# ElectroLab.net
KiCad netlist of a schematic drawn in EAGLE
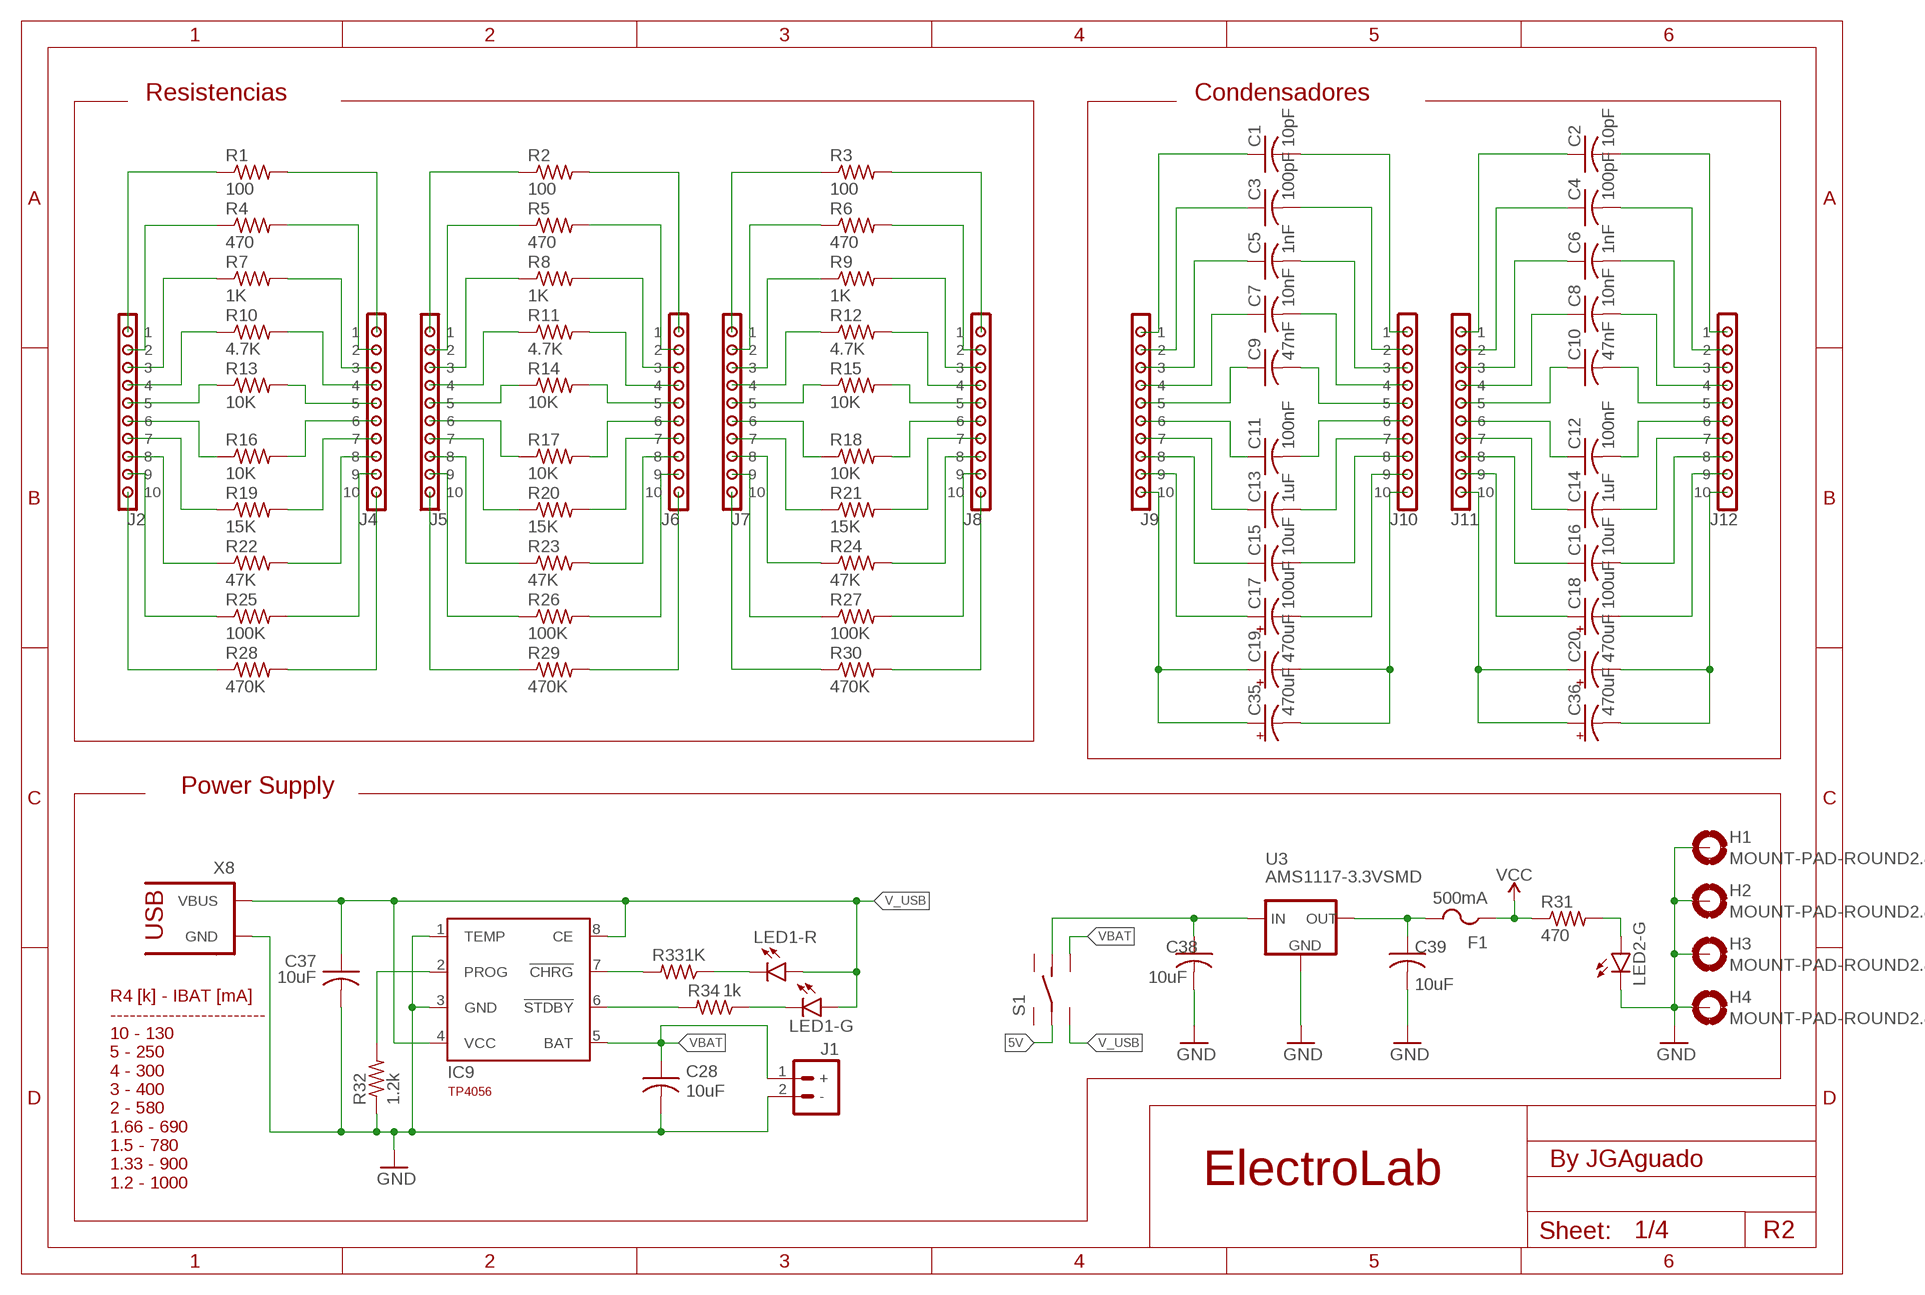
[diagram p0: schematic, sheet 1]
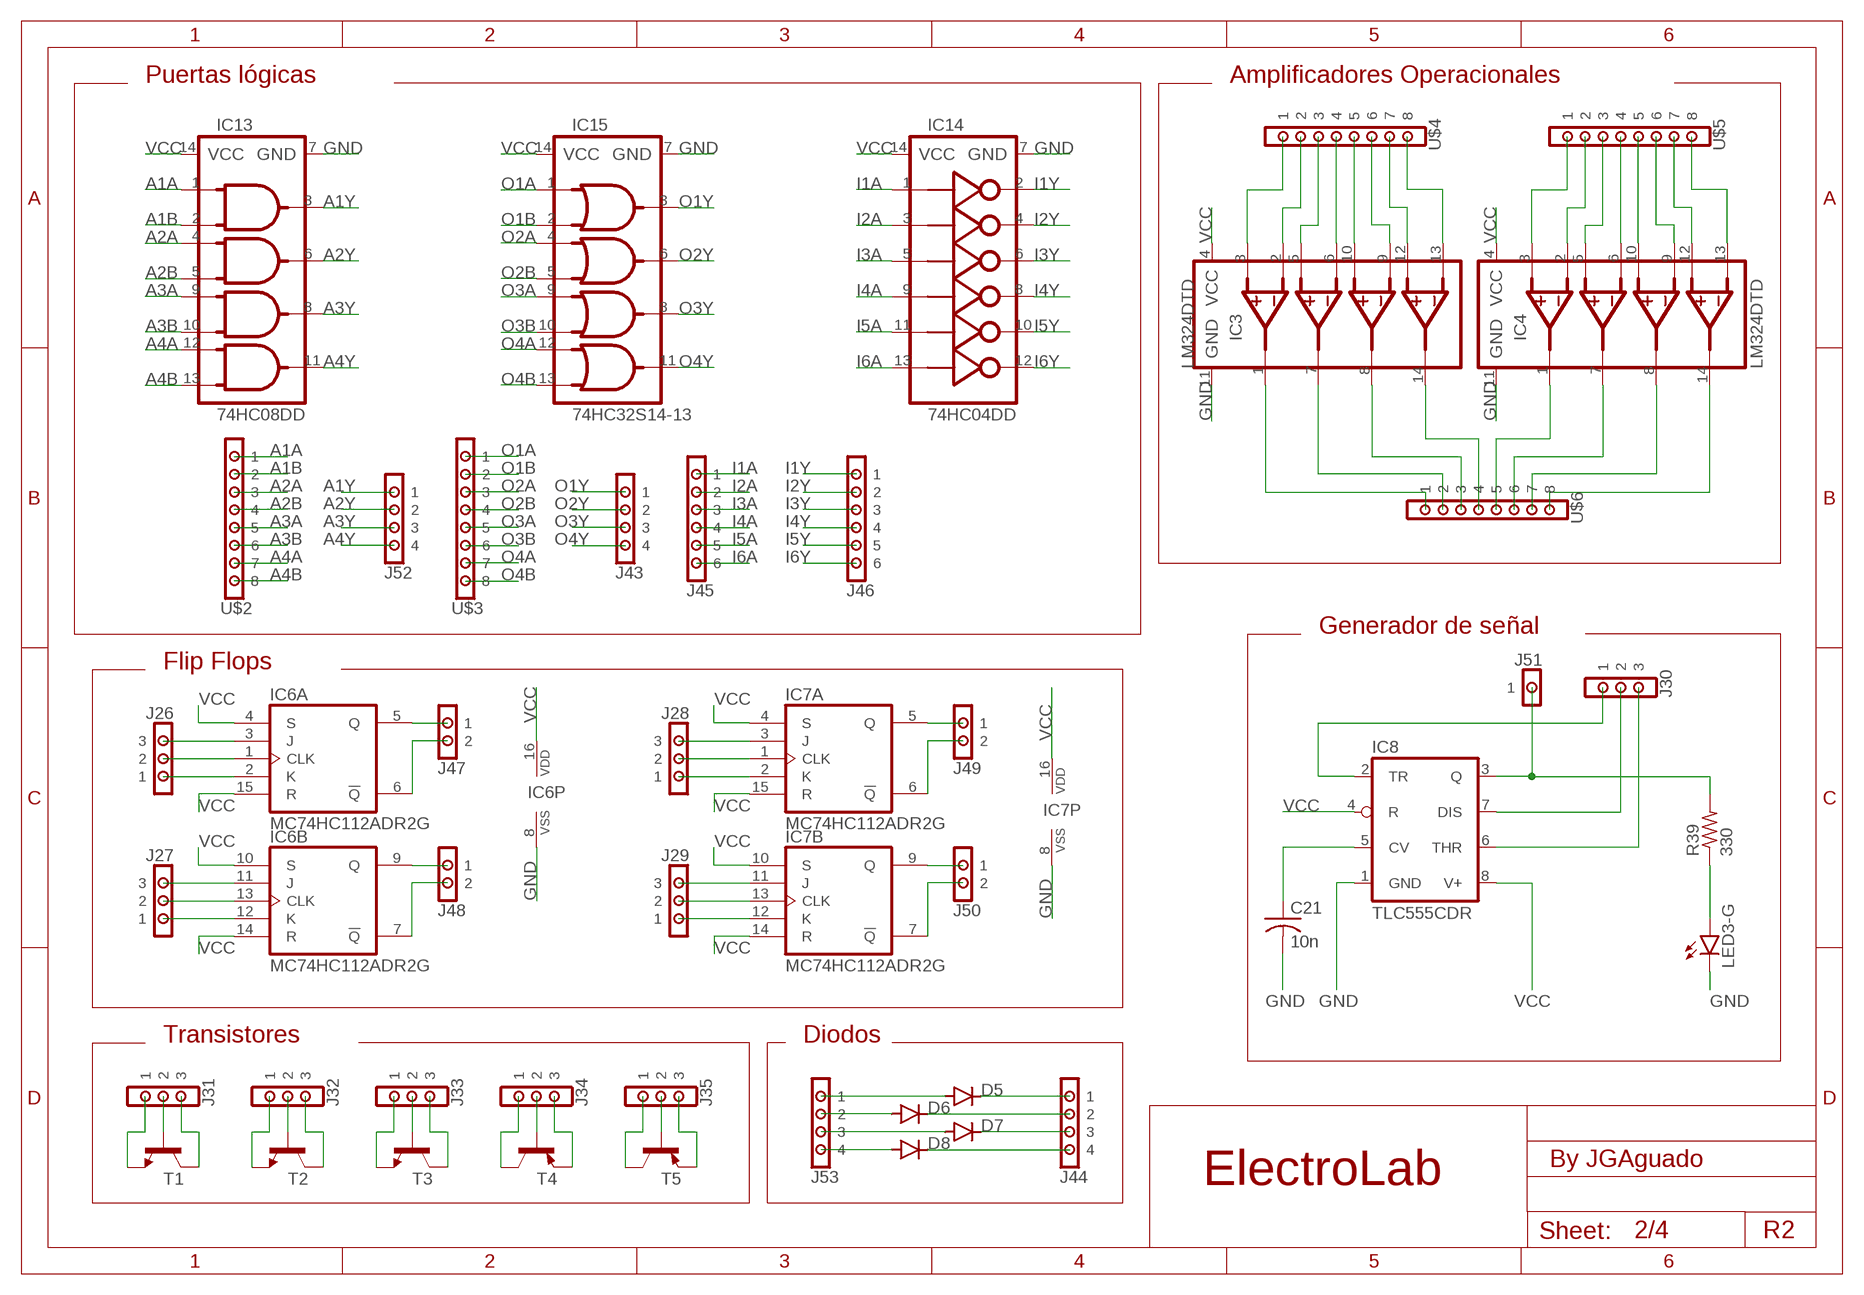
[diagram p1: schematic, sheet 2]
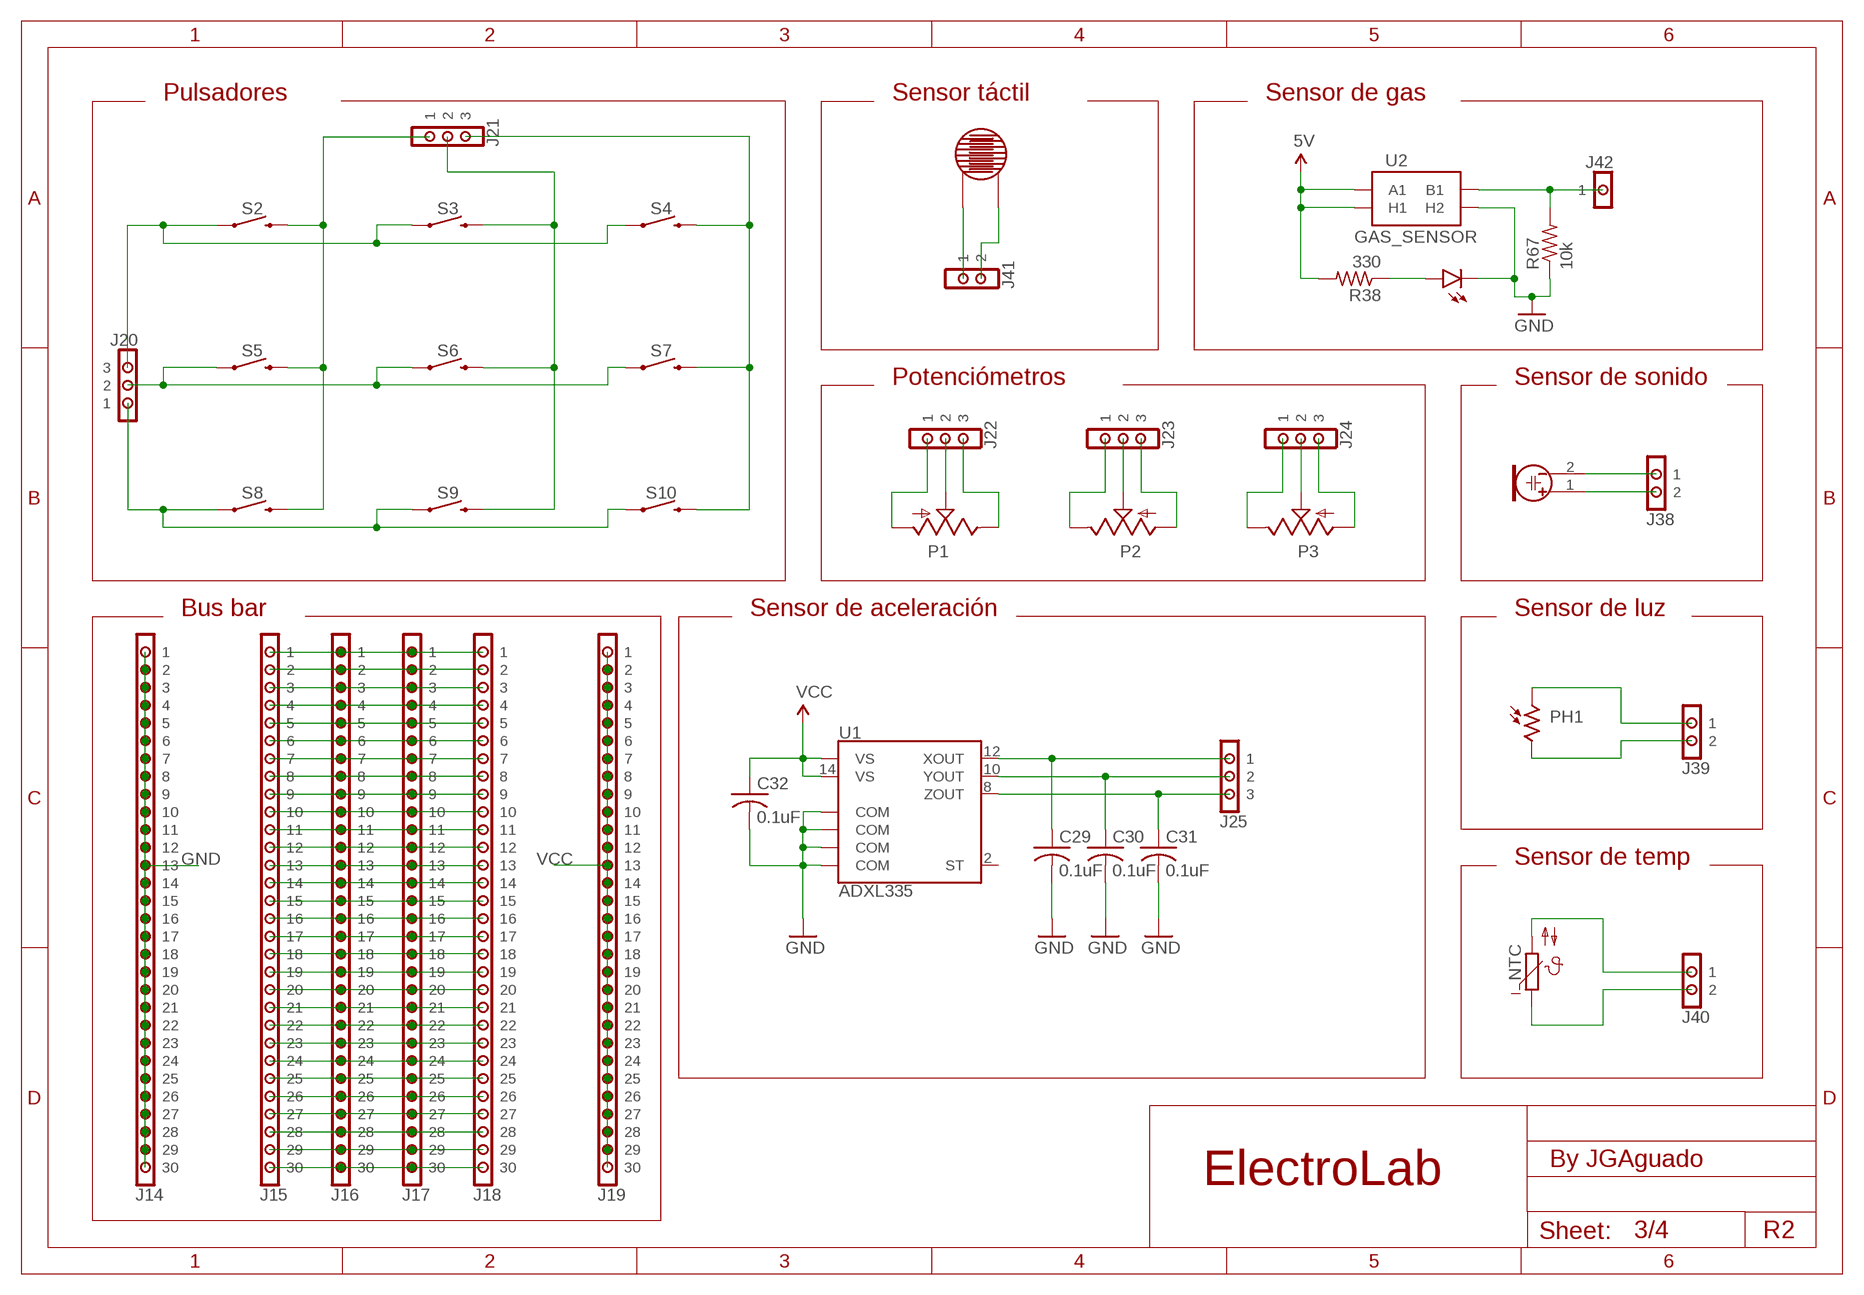
[diagram p2: schematic, sheet 3]
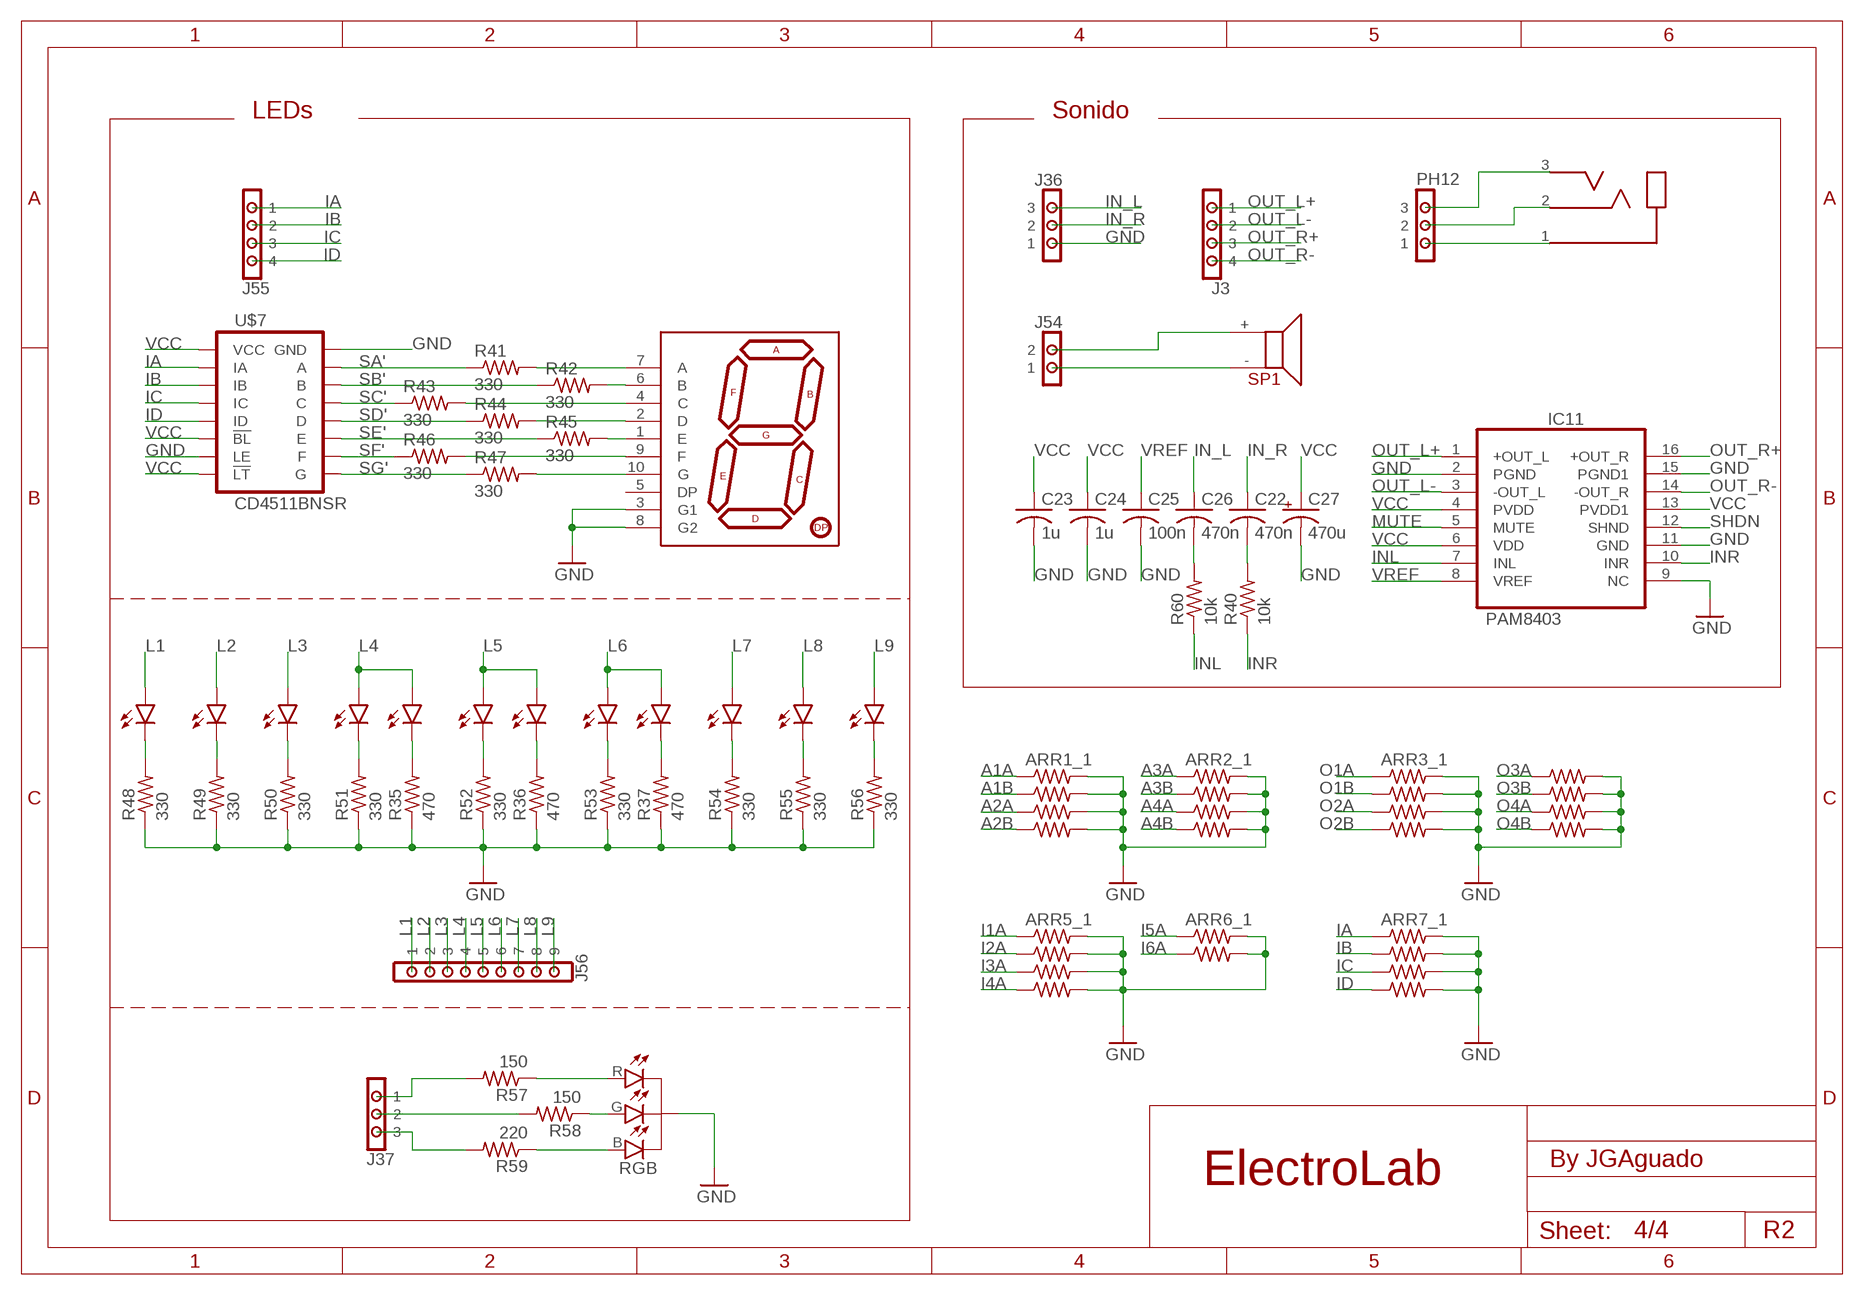
[diagram p3: schematic, sheet 4]

(export (version "E")
  (design (tool "Eeschema 10.0.6"))
  (components
    (comp (ref "C1")
      (value "10pF")
      (footprint "eagle-import:0603")
      (libsource (lib "eagle-import") (part "C0603"))
    )
    (comp (ref "C2")
      (value "10pF")
      (footprint "eagle-import:0603")
      (libsource (lib "eagle-import") (part "C0603"))
    )
    (comp (ref "C3")
      (value "100pF")
      (footprint "eagle-import:0603")
      (libsource (lib "eagle-import") (part "C0603"))
    )
    (comp (ref "C4")
      (value "100pF")
      (footprint "eagle-import:0603")
      (libsource (lib "eagle-import") (part "C0603"))
    )
    (comp (ref "C5")
      (value "1nF")
      (footprint "eagle-import:0603")
      (libsource (lib "eagle-import") (part "C0603"))
    )
    (comp (ref "C6")
      (value "1nF")
      (footprint "eagle-import:0603")
      (libsource (lib "eagle-import") (part "C0603"))
    )
    (comp (ref "C7")
      (value "10nF")
      (footprint "eagle-import:0603")
      (libsource (lib "eagle-import") (part "C0603"))
    )
    (comp (ref "C8")
      (value "10nF")
      (footprint "eagle-import:0603")
      (libsource (lib "eagle-import") (part "C0603"))
    )
    (comp (ref "C9")
      (value "47nF")
      (footprint "eagle-import:0603")
      (libsource (lib "eagle-import") (part "C0603"))
    )
    (comp (ref "C10")
      (value "47nF")
      (footprint "eagle-import:0603")
      (libsource (lib "eagle-import") (part "C0603"))
    )
    (comp (ref "C11")
      (value "100nF")
      (footprint "eagle-import:0603")
      (libsource (lib "eagle-import") (part "C0603"))
    )
    (comp (ref "C12")
      (value "100nF")
      (footprint "eagle-import:0603")
      (libsource (lib "eagle-import") (part "C0603"))
    )
    (comp (ref "C13")
      (value "1uF")
      (footprint "eagle-import:0603")
      (libsource (lib "eagle-import") (part "C0603"))
    )
    (comp (ref "C14")
      (value "1uF")
      (footprint "eagle-import:0603")
      (libsource (lib "eagle-import") (part "C0603"))
    )
    (comp (ref "C15")
      (value "10uF")
      (footprint "eagle-import:0603")
      (libsource (lib "eagle-import") (part "C0603"))
    )
    (comp (ref "C16")
      (value "10uF")
      (footprint "eagle-import:0603")
      (libsource (lib "eagle-import") (part "C0603"))
    )
    (comp (ref "C17")
      (value "100uF")
      (footprint "eagle-import:B_3528-21R")
      (libsource (lib "eagle-import") (part "C3528"))
    )
    (comp (ref "C18")
      (value "100uF")
      (footprint "eagle-import:B_3528-21R")
      (libsource (lib "eagle-import") (part "C3528"))
    )
    (comp (ref "C19")
      (value "470uF")
      (footprint "eagle-import:D_7343-31R")
      (libsource (lib "eagle-import") (part "C7343"))
    )
    (comp (ref "C20")
      (value "470uF")
      (footprint "eagle-import:D_7343-31R")
      (libsource (lib "eagle-import") (part "C7343"))
    )
    (comp (ref "C28")
      (value "10uF")
      (footprint "eagle-import:C0603")
      (libsource (lib "eagle-import") (part "C-USC0603"))
    )
    (comp (ref "C35")
      (value "470uF")
      (footprint "eagle-import:D_7343-31R")
      (libsource (lib "eagle-import") (part "C7343"))
    )
    (comp (ref "C36")
      (value "470uF")
      (footprint "eagle-import:D_7343-31R")
      (libsource (lib "eagle-import") (part "C7343"))
    )
    (comp (ref "C37")
      (value "10uF")
      (footprint "eagle-import:C0603")
      (libsource (lib "eagle-import") (part "C-USC0603"))
    )
    (comp (ref "C38")
      (value "10uF")
      (footprint "eagle-import:C0603")
      (libsource (lib "eagle-import") (part "C-USC0603"))
    )
    (comp (ref "C39")
      (value "10uF")
      (footprint "eagle-import:C0603")
      (libsource (lib "eagle-import") (part "C-USC0603"))
    )
    (comp (ref "F1")
      (value "500mA")
      (footprint "eagle-import:R1206")
      (libsource (lib "eagle-import") (part "PTCFUSE-1206"))
    )
    (comp (ref "H1")
      (value "MOUNT-PAD-ROUND2.8")
      (footprint "eagle-import:2,8-PAD")
      (libsource (lib "eagle-import") (part "MOUNT-PAD-ROUND2.8"))
    )
    (comp (ref "H2")
      (value "MOUNT-PAD-ROUND2.8")
      (footprint "eagle-import:2,8-PAD")
      (libsource (lib "eagle-import") (part "MOUNT-PAD-ROUND2.8"))
    )
    (comp (ref "H3")
      (value "MOUNT-PAD-ROUND2.8")
      (footprint "eagle-import:2,8-PAD")
      (libsource (lib "eagle-import") (part "MOUNT-PAD-ROUND2.8"))
    )
    (comp (ref "H4")
      (value "MOUNT-PAD-ROUND2.8")
      (footprint "eagle-import:2,8-PAD")
      (libsource (lib "eagle-import") (part "MOUNT-PAD-ROUND2.8"))
    )
    (comp (ref "IC9")
      (value "TP4056")
      (footprint "eagle-import:SOT23-8")
      (libsource (lib "eagle-import") (part "TP4056"))
    )
    (comp (ref "J1")
      (value "BAT_CONN-JST-2MM-SMT")
      (footprint "eagle-import:JST-2-SMD")
      (fields (field (name "LCSC") "C3029440"))
      (libsource (lib "eagle-import") (part "BAT_CONN-JST-2MM-SMT"))
    )
    (comp (ref "J2")
      (value "CONN_10\"")
      (footprint "eagle-import:1X10")
      (libsource (lib "eagle-import") (part "CONN_10{dblquote}"))
    )
    (comp (ref "J4")
      (value "CONN_10\"")
      (footprint "eagle-import:1X10")
      (libsource (lib "eagle-import") (part "CONN_10{dblquote}"))
    )
    (comp (ref "J5")
      (value "CONN_10\"")
      (footprint "eagle-import:1X10")
      (libsource (lib "eagle-import") (part "CONN_10{dblquote}"))
    )
    (comp (ref "J6")
      (value "CONN_10\"")
      (footprint "eagle-import:1X10")
      (libsource (lib "eagle-import") (part "CONN_10{dblquote}"))
    )
    (comp (ref "J7")
      (value "CONN_10\"")
      (footprint "eagle-import:1X10")
      (libsource (lib "eagle-import") (part "CONN_10{dblquote}"))
    )
    (comp (ref "J8")
      (value "CONN_10\"")
      (footprint "eagle-import:1X10")
      (libsource (lib "eagle-import") (part "CONN_10{dblquote}"))
    )
    (comp (ref "J9")
      (value "CONN_10\"")
      (footprint "eagle-import:1X10")
      (libsource (lib "eagle-import") (part "CONN_10{dblquote}"))
    )
    (comp (ref "J10")
      (value "CONN_10\"")
      (footprint "eagle-import:1X10")
      (libsource (lib "eagle-import") (part "CONN_10{dblquote}"))
    )
    (comp (ref "J11")
      (value "CONN_10\"")
      (footprint "eagle-import:1X10")
      (libsource (lib "eagle-import") (part "CONN_10{dblquote}"))
    )
    (comp (ref "J12")
      (value "CONN_10\"")
      (footprint "eagle-import:1X10")
      (libsource (lib "eagle-import") (part "CONN_10{dblquote}"))
    )
    (comp (ref "LED1")
      (value "E6CC1205RYGC2UDA")
      (footprint "eagle-import:BICOLOR_LED")
      (libsource (lib "eagle-import") (part "RED&GREEN_LED"))
    )
    (comp (ref "LED2")
      (value "E6CC1205RYGC2UDA")
      (footprint "eagle-import:BICOLOR_LED")
      (libsource (lib "eagle-import") (part "RED&GREEN_LED"))
    )
    (comp (ref "R1")
      (value "100")
      (footprint "eagle-import:0603")
      (libsource (lib "eagle-import") (part "R0603"))
    )
    (comp (ref "R2")
      (value "100")
      (footprint "eagle-import:0603")
      (libsource (lib "eagle-import") (part "R0603"))
    )
    (comp (ref "R3")
      (value "100")
      (footprint "eagle-import:0603")
      (libsource (lib "eagle-import") (part "R0603"))
    )
    (comp (ref "R4")
      (value "470")
      (footprint "eagle-import:0603")
      (libsource (lib "eagle-import") (part "R0603"))
    )
    (comp (ref "R5")
      (value "470")
      (footprint "eagle-import:0603")
      (libsource (lib "eagle-import") (part "R0603"))
    )
    (comp (ref "R6")
      (value "470")
      (footprint "eagle-import:0603")
      (libsource (lib "eagle-import") (part "R0603"))
    )
    (comp (ref "R7")
      (value "1K")
      (footprint "eagle-import:0603")
      (libsource (lib "eagle-import") (part "R0603"))
    )
    (comp (ref "R8")
      (value "1K")
      (footprint "eagle-import:0603")
      (libsource (lib "eagle-import") (part "R0603"))
    )
    (comp (ref "R9")
      (value "1K")
      (footprint "eagle-import:0603")
      (libsource (lib "eagle-import") (part "R0603"))
    )
    (comp (ref "R10")
      (value "4.7K")
      (footprint "eagle-import:0603")
      (libsource (lib "eagle-import") (part "R0603"))
    )
    (comp (ref "R11")
      (value "4.7K")
      (footprint "eagle-import:0603")
      (libsource (lib "eagle-import") (part "R0603"))
    )
    (comp (ref "R12")
      (value "4.7K")
      (footprint "eagle-import:0603")
      (libsource (lib "eagle-import") (part "R0603"))
    )
    (comp (ref "R13")
      (value "10K")
      (footprint "eagle-import:0603")
      (libsource (lib "eagle-import") (part "R0603"))
    )
    (comp (ref "R14")
      (value "10K")
      (footprint "eagle-import:0603")
      (libsource (lib "eagle-import") (part "R0603"))
    )
    (comp (ref "R15")
      (value "10K")
      (footprint "eagle-import:0603")
      (libsource (lib "eagle-import") (part "R0603"))
    )
    (comp (ref "R16")
      (value "10K")
      (footprint "eagle-import:0603")
      (libsource (lib "eagle-import") (part "R0603"))
    )
    (comp (ref "R17")
      (value "10K")
      (footprint "eagle-import:0603")
      (libsource (lib "eagle-import") (part "R0603"))
    )
    (comp (ref "R18")
      (value "10K")
      (footprint "eagle-import:0603")
      (libsource (lib "eagle-import") (part "R0603"))
    )
    (comp (ref "R19")
      (value "15K")
      (footprint "eagle-import:0603")
      (libsource (lib "eagle-import") (part "R0603"))
    )
    (comp (ref "R20")
      (value "15K")
      (footprint "eagle-import:0603")
      (libsource (lib "eagle-import") (part "R0603"))
    )
    (comp (ref "R21")
      (value "15K")
      (footprint "eagle-import:0603")
      (libsource (lib "eagle-import") (part "R0603"))
    )
    (comp (ref "R22")
      (value "47K")
      (footprint "eagle-import:0603")
      (libsource (lib "eagle-import") (part "R0603"))
    )
    (comp (ref "R23")
      (value "47K")
      (footprint "eagle-import:0603")
      (libsource (lib "eagle-import") (part "R0603"))
    )
    (comp (ref "R24")
      (value "47K")
      (footprint "eagle-import:0603")
      (libsource (lib "eagle-import") (part "R0603"))
    )
    (comp (ref "R25")
      (value "100K")
      (footprint "eagle-import:0603")
      (libsource (lib "eagle-import") (part "R0603"))
    )
    (comp (ref "R26")
      (value "100K")
      (footprint "eagle-import:0603")
      (libsource (lib "eagle-import") (part "R0603"))
    )
    (comp (ref "R27")
      (value "100K")
      (footprint "eagle-import:0603")
      (libsource (lib "eagle-import") (part "R0603"))
    )
    (comp (ref "R28")
      (value "470K")
      (footprint "eagle-import:0603")
      (libsource (lib "eagle-import") (part "R0603"))
    )
    (comp (ref "R29")
      (value "470K")
      (footprint "eagle-import:0603")
      (libsource (lib "eagle-import") (part "R0603"))
    )
    (comp (ref "R30")
      (value "470K")
      (footprint "eagle-import:0603")
      (libsource (lib "eagle-import") (part "R0603"))
    )
    (comp (ref "R31")
      (value "470")
      (footprint "eagle-import:0603")
      (libsource (lib "eagle-import") (part "R0603"))
    )
    (comp (ref "R32")
      (value "1.2k")
      (footprint "eagle-import:R0603")
      (libsource (lib "eagle-import") (part "R-US_R0603"))
    )
    (comp (ref "R33")
      (value "1K")
      (footprint "eagle-import:0603")
      (libsource (lib "eagle-import") (part "R0603"))
    )
    (comp (ref "R34")
      (value "1k")
      (footprint "eagle-import:0603")
      (libsource (lib "eagle-import") (part "R0603"))
    )
    (comp (ref "S1")
      (value "DPDT_JS202011CQN")
      (footprint "eagle-import:DPDT_JS202011CQN")
      (libsource (lib "eagle-import") (part "DPDT_JS202011CQN"))
    )
    (comp (ref "U3")
      (value "AMS1117-3.3VSMD")
      (footprint "eagle-import:SOT223")
      (libsource (lib "eagle-import") (part "AMS1117-SMD3.3V"))
    )
    (comp (ref "X8")
      (value "USB-C-POWER")
      (footprint "eagle-import:USB-C-POWER")
      (libsource (lib "eagle-import") (part "USB-C-POWER"))
    )
    (comp (ref "C21")
      (value "10n")
      (footprint "eagle-import:0603")
      (libsource (lib "eagle-import") (part "C0603"))
    )
    (comp (ref "D5")
      (value "LL4148")
      (footprint "eagle-import:LL-34")
      (fields (field (name "MOUSER_PART_NUMBER") "512-LL4148"))
      (libsource (lib "eagle-import") (part "LL4148"))
    )
    (comp (ref "D6")
      (value "LL4148")
      (footprint "eagle-import:LL-34")
      (fields (field (name "MOUSER_PART_NUMBER") "512-LL4148"))
      (libsource (lib "eagle-import") (part "LL4148"))
    )
    (comp (ref "D7")
      (value "LL4148")
      (footprint "eagle-import:LL-34")
      (fields (field (name "MOUSER_PART_NUMBER") "512-LL4148"))
      (libsource (lib "eagle-import") (part "LL4148"))
    )
    (comp (ref "D8")
      (value "LL4148")
      (footprint "eagle-import:LL-34")
      (fields (field (name "MOUSER_PART_NUMBER") "512-LL4148"))
      (libsource (lib "eagle-import") (part "LL4148"))
    )
    (comp (ref "IC3")
      (value "LM324DTD")
      (footprint "eagle-import:SO14")
      (libsource (lib "eagle-import") (part "LM324DTD"))
    )
    (comp (ref "IC4")
      (value "LM324DTD")
      (footprint "eagle-import:SO14")
      (libsource (lib "eagle-import") (part "LM324DTD"))
    )
    (comp (ref "IC6")
      (value "MC74HC112ADR2G")
      (footprint "eagle-import:SO16")
      (libsource (lib "eagle-import") (part "JK_FLIP_FLOPMC74HC112ADR2G"))
    )
    (comp (ref "IC7")
      (value "MC74HC112ADR2G")
      (footprint "eagle-import:SO16")
      (libsource (lib "eagle-import") (part "JK_FLIP_FLOPMC74HC112ADR2G"))
    )
    (comp (ref "IC8")
      (value "TLC555CDR")
      (footprint "eagle-import:SO08")
      (libsource (lib "eagle-import") (part "555DNE"))
    )
    (comp (ref "IC13")
      (value "74HC08DD")
      (footprint "eagle-import:SO14")
      (libsource (lib "eagle-import") (part "74HC08DD"))
    )
    (comp (ref "IC14")
      (value "74HC04DD")
      (footprint "eagle-import:SO14")
      (libsource (lib "eagle-import") (part "74HC04DD"))
    )
    (comp (ref "IC15")
      (value "74HC32S14-13")
      (footprint "eagle-import:SO14")
      (fields (field (name "LCSC") "C176921"))
      (libsource (lib "eagle-import") (part "74AHC32D74HC32S14-13"))
    )
    (comp (ref "J26")
      (value "CONN_03")
      (footprint "eagle-import:1X03")
      (libsource (lib "eagle-import") (part "CONN_03"))
    )
    (comp (ref "J27")
      (value "CONN_03")
      (footprint "eagle-import:1X03")
      (libsource (lib "eagle-import") (part "CONN_03"))
    )
    (comp (ref "J28")
      (value "CONN_03")
      (footprint "eagle-import:1X03")
      (libsource (lib "eagle-import") (part "CONN_03"))
    )
    (comp (ref "J29")
      (value "CONN_03")
      (footprint "eagle-import:1X03")
      (libsource (lib "eagle-import") (part "CONN_03"))
    )
    (comp (ref "J30")
      (value "CONN_03")
      (footprint "eagle-import:1X03")
      (libsource (lib "eagle-import") (part "CONN_03"))
    )
    (comp (ref "J31")
      (value "CONN_03")
      (footprint "eagle-import:1X03")
      (libsource (lib "eagle-import") (part "CONN_03"))
    )
    (comp (ref "J32")
      (value "CONN_03")
      (footprint "eagle-import:1X03")
      (libsource (lib "eagle-import") (part "CONN_03"))
    )
    (comp (ref "J33")
      (value "CONN_03")
      (footprint "eagle-import:1X03")
      (libsource (lib "eagle-import") (part "CONN_03"))
    )
    (comp (ref "J34")
      (value "CONN_03")
      (footprint "eagle-import:1X03")
      (libsource (lib "eagle-import") (part "CONN_03"))
    )
    (comp (ref "J35")
      (value "CONN_03")
      (footprint "eagle-import:1X03")
      (libsource (lib "eagle-import") (part "CONN_03"))
    )
    (comp (ref "J43")
      (value "CONN_04")
      (footprint "eagle-import:1X04")
      (libsource (lib "eagle-import") (part "CONN_04"))
    )
    (comp (ref "J44")
      (value "CONN_04")
      (footprint "eagle-import:1X04")
      (libsource (lib "eagle-import") (part "CONN_04"))
    )
    (comp (ref "J45")
      (value "CONN_06")
      (footprint "eagle-import:1X06")
      (libsource (lib "eagle-import") (part "CONN_06"))
    )
    (comp (ref "J46")
      (value "CONN_06")
      (footprint "eagle-import:1X06")
      (libsource (lib "eagle-import") (part "CONN_06"))
    )
    (comp (ref "J47")
      (value "CONN_02")
      (footprint "eagle-import:1X02")
      (libsource (lib "eagle-import") (part "CONN_02"))
    )
    (comp (ref "J48")
      (value "CONN_02")
      (footprint "eagle-import:1X02")
      (libsource (lib "eagle-import") (part "CONN_02"))
    )
    (comp (ref "J49")
      (value "CONN_02")
      (footprint "eagle-import:1X02")
      (libsource (lib "eagle-import") (part "CONN_02"))
    )
    (comp (ref "J50")
      (value "CONN_02")
      (footprint "eagle-import:1X02")
      (libsource (lib "eagle-import") (part "CONN_02"))
    )
    (comp (ref "J51")
      (value "CONN_01")
      (footprint "eagle-import:1X01")
      (libsource (lib "eagle-import") (part "CONN_01"))
    )
    (comp (ref "J52")
      (value "CONN_04")
      (footprint "eagle-import:1X04")
      (libsource (lib "eagle-import") (part "CONN_04"))
    )
    (comp (ref "J53")
      (value "CONN_04")
      (footprint "eagle-import:1X04")
      (libsource (lib "eagle-import") (part "CONN_04"))
    )
    (comp (ref "LED3")
      (value "E6CC1205RYGC2UDA")
      (footprint "eagle-import:BICOLOR_LED")
      (libsource (lib "eagle-import") (part "RED&GREEN_LED"))
    )
    (comp (ref "R39")
      (value "330")
      (footprint "eagle-import:0603")
      (libsource (lib "eagle-import") (part "R0603"))
    )
    (comp (ref "T1")
      (value "MMBT2222A")
      (footprint "eagle-import:SOT23")
      (fields (field (name "LCSC_PART") "C8512"))
      (libsource (lib "eagle-import") (part "T_NPN_SOT23-BECMMBT2222A-1P_CHANGJ"))
    )
    (comp (ref "T2")
      (value "T_NPNMMBT2222A-1P_CHANGJ_SOT23-BEC")
      (footprint "eagle-import:SOT23")
      (fields (field (name "LCSC_PART") "C8512"))
      (libsource (lib "eagle-import") (part "T_NPN_SOT23-BECMMBT2222A-1P_CHANGJ"))
    )
    (comp (ref "T3")
      (value "T_NPNMMBT2222A-1P_CHANGJ_SOT23-BEC")
      (footprint "eagle-import:SOT23")
      (fields (field (name "LCSC_PART") "C8512"))
      (libsource (lib "eagle-import") (part "T_NPN_SOT23-BECMMBT2222A-1P_CHANGJ"))
    )
    (comp (ref "T4")
      (value "T_PNPMMBT5401_CHANGJ_SOT23-BEC")
      (footprint "eagle-import:SOT23")
      (fields (field (name "LCSC_PART") "C8326"))
      (libsource (lib "eagle-import") (part "T_PNP_SOT23-BECMMBT5401_CHANGJ"))
    )
    (comp (ref "T5")
      (value "T_PNPMMBT5401_CHANGJ_SOT23-BEC")
      (footprint "eagle-import:SOT23")
      (fields (field (name "LCSC_PART") "C8326"))
      (libsource (lib "eagle-import") (part "T_PNP_SOT23-BECMMBT5401_CHANGJ"))
    )
    (comp (ref "U$2")
      (value "CONN_08")
      (footprint "eagle-import:1X08")
      (libsource (lib "eagle-import") (part "CONN_08"))
    )
    (comp (ref "U$3")
      (value "CONN_08")
      (footprint "eagle-import:1X08")
      (libsource (lib "eagle-import") (part "CONN_08"))
    )
    (comp (ref "U$4")
      (value "CONN_08")
      (footprint "eagle-import:1X08")
      (libsource (lib "eagle-import") (part "CONN_08"))
    )
    (comp (ref "U$5")
      (value "CONN_08")
      (footprint "eagle-import:1X08")
      (libsource (lib "eagle-import") (part "CONN_08"))
    )
    (comp (ref "U$6")
      (value "CONN_08")
      (footprint "eagle-import:1X08")
      (libsource (lib "eagle-import") (part "CONN_08"))
    )
    (comp (ref "C29")
      (value "0.1uF")
      (footprint "eagle-import:0603")
      (libsource (lib "eagle-import") (part "C0603"))
    )
    (comp (ref "C30")
      (value "0.1uF")
      (footprint "eagle-import:0603")
      (libsource (lib "eagle-import") (part "C0603"))
    )
    (comp (ref "C31")
      (value "0.1uF")
      (footprint "eagle-import:0603")
      (libsource (lib "eagle-import") (part "C0603"))
    )
    (comp (ref "C32")
      (value "0.1uF")
      (footprint "eagle-import:0603")
      (libsource (lib "eagle-import") (part "C0603"))
    )
    (comp (ref "J14")
      (value "CONN_30")
      (footprint "eagle-import:1X30")
      (libsource (lib "eagle-import") (part "CONN_30"))
    )
    (comp (ref "J15")
      (value "CONN_30")
      (footprint "eagle-import:1X30")
      (libsource (lib "eagle-import") (part "CONN_30"))
    )
    (comp (ref "J16")
      (value "CONN_30")
      (footprint "eagle-import:1X30")
      (libsource (lib "eagle-import") (part "CONN_30"))
    )
    (comp (ref "J17")
      (value "CONN_30")
      (footprint "eagle-import:1X30")
      (libsource (lib "eagle-import") (part "CONN_30"))
    )
    (comp (ref "J18")
      (value "CONN_30")
      (footprint "eagle-import:1X30")
      (libsource (lib "eagle-import") (part "CONN_30"))
    )
    (comp (ref "J19")
      (value "CONN_30")
      (footprint "eagle-import:1X30")
      (libsource (lib "eagle-import") (part "CONN_30"))
    )
    (comp (ref "J20")
      (value "CONN_03")
      (footprint "eagle-import:1X03")
      (libsource (lib "eagle-import") (part "CONN_03"))
    )
    (comp (ref "J21")
      (value "CONN_03")
      (footprint "eagle-import:1X03")
      (libsource (lib "eagle-import") (part "CONN_03"))
    )
    (comp (ref "J22")
      (value "CONN_03")
      (footprint "eagle-import:1X03")
      (libsource (lib "eagle-import") (part "CONN_03"))
    )
    (comp (ref "J23")
      (value "CONN_03")
      (footprint "eagle-import:1X03")
      (libsource (lib "eagle-import") (part "CONN_03"))
    )
    (comp (ref "J24")
      (value "CONN_03")
      (footprint "eagle-import:1X03")
      (libsource (lib "eagle-import") (part "CONN_03"))
    )
    (comp (ref "J25")
      (value "CONN_03")
      (footprint "eagle-import:1X03")
      (libsource (lib "eagle-import") (part "CONN_03"))
    )
    (comp (ref "J38")
      (value "CONN_02")
      (footprint "eagle-import:1X02")
      (libsource (lib "eagle-import") (part "CONN_02"))
    )
    (comp (ref "J39")
      (value "CONN_02")
      (footprint "eagle-import:1X02")
      (libsource (lib "eagle-import") (part "CONN_02"))
    )
    (comp (ref "J40")
      (value "CONN_02")
      (footprint "eagle-import:1X02")
      (libsource (lib "eagle-import") (part "CONN_02"))
    )
    (comp (ref "J41")
      (value "CONN_02")
      (footprint "eagle-import:1X02")
      (libsource (lib "eagle-import") (part "CONN_02"))
    )
    (comp (ref "J42")
      (value "CONN_01")
      (footprint "eagle-import:1X01")
      (libsource (lib "eagle-import") (part "CONN_01"))
    )
    (comp (ref "LED13")
      (value "E6CC1205RYGC2UDA")
      (footprint "eagle-import:BICOLOR_LED")
      (libsource (lib "eagle-import") (part "RED&GREEN_LED"))
    )
    (comp (ref "MIC")
      (value "MICROPHONE")
      (footprint "eagle-import:MICROPHONE")
      (libsource (lib "eagle-import") (part "MICROPHONE"))
    )
    (comp (ref "NTC")
      (value "THERMISTOR")
      (footprint "eagle-import:NTC")
      (libsource (lib "eagle-import") (part "THERMISTOR"))
    )
    (comp (ref "P1")
      (value "SLIDE_POT_20MM")
      (footprint "eagle-import:RS201111J011")
      (libsource (lib "eagle-import") (part "SLIDE_POT_20MM"))
    )
    (comp (ref "P2")
      (value "ALPS_RK09K_VERTICAL")
      (footprint "eagle-import:ALPS_RK09K_VERTICAL")
      (libsource (lib "eagle-import") (part "ALPS_RK09K_VERTICAL"))
    )
    (comp (ref "P3")
      (value "ALPS_RK09K_VERTICAL")
      (footprint "eagle-import:ALPS_RK09K_VERTICAL")
      (libsource (lib "eagle-import") (part "ALPS_RK09K_VERTICAL"))
    )
    (comp (ref "PH1")
      (value "PHOTORESISTOR")
      (footprint "eagle-import:GL5516")
      (libsource (lib "eagle-import") (part "PHOTORESISTOR"))
    )
    (comp (ref "R38")
      (value "330")
      (footprint "eagle-import:0603")
      (libsource (lib "eagle-import") (part "R0603"))
    )
    (comp (ref "R67")
      (value "10k")
      (footprint "eagle-import:0603")
      (libsource (lib "eagle-import") (part "R0603"))
    )
    (comp (ref "S2")
      (value "MOMENTARY-SWITCH-SPST-PTH-6.0MM")
      (footprint "eagle-import:TACTILE_SWITCH_PTH_6.0MM")
      (libsource (lib "eagle-import") (part "MOMENTARY-SWITCH-SPST-PTH-6.0MM"))
    )
    (comp (ref "S3")
      (value "MOMENTARY-SWITCH-SPST-PTH-6.0MM")
      (footprint "eagle-import:TACTILE_SWITCH_PTH_6.0MM")
      (libsource (lib "eagle-import") (part "MOMENTARY-SWITCH-SPST-PTH-6.0MM"))
    )
    (comp (ref "S4")
      (value "MOMENTARY-SWITCH-SPST-PTH-6.0MM")
      (footprint "eagle-import:TACTILE_SWITCH_PTH_6.0MM")
      (libsource (lib "eagle-import") (part "MOMENTARY-SWITCH-SPST-PTH-6.0MM"))
    )
    (comp (ref "S5")
      (value "MOMENTARY-SWITCH-SPST-PTH-6.0MM")
      (footprint "eagle-import:TACTILE_SWITCH_PTH_6.0MM")
      (libsource (lib "eagle-import") (part "MOMENTARY-SWITCH-SPST-PTH-6.0MM"))
    )
    (comp (ref "S6")
      (value "MOMENTARY-SWITCH-SPST-PTH-6.0MM")
      (footprint "eagle-import:TACTILE_SWITCH_PTH_6.0MM")
      (libsource (lib "eagle-import") (part "MOMENTARY-SWITCH-SPST-PTH-6.0MM"))
    )
    (comp (ref "S7")
      (value "MOMENTARY-SWITCH-SPST-PTH-6.0MM")
      (footprint "eagle-import:TACTILE_SWITCH_PTH_6.0MM")
      (libsource (lib "eagle-import") (part "MOMENTARY-SWITCH-SPST-PTH-6.0MM"))
    )
    (comp (ref "S8")
      (value "MOMENTARY-SWITCH-SPST-PTH-6.0MM")
      (footprint "eagle-import:TACTILE_SWITCH_PTH_6.0MM")
      (libsource (lib "eagle-import") (part "MOMENTARY-SWITCH-SPST-PTH-6.0MM"))
    )
    (comp (ref "S9")
      (value "MOMENTARY-SWITCH-SPST-PTH-6.0MM")
      (footprint "eagle-import:TACTILE_SWITCH_PTH_6.0MM")
      (libsource (lib "eagle-import") (part "MOMENTARY-SWITCH-SPST-PTH-6.0MM"))
    )
    (comp (ref "S10")
      (value "MOMENTARY-SWITCH-SPST-PTH-6.0MM")
      (footprint "eagle-import:TACTILE_SWITCH_PTH_6.0MM")
      (libsource (lib "eagle-import") (part "MOMENTARY-SWITCH-SPST-PTH-6.0MM"))
    )
    (comp (ref "U$16")
      (value "RESISTIVE_SENSOR_PAD")
      (footprint "eagle-import:RESISTIVE_SENSOR_PAD")
      (libsource (lib "eagle-import") (part "RESISTIVE_SENSOR_PAD"))
    )
    (comp (ref "U1")
      (value "ADXL335")
      (footprint "eagle-import:LFCSP-16-4X4")
      (libsource (lib "eagle-import") (part "ADXL335"))
    )
    (comp (ref "U2")
      (value "GAS_SENSOR")
      (footprint "eagle-import:GAS_SENSOR")
      (libsource (lib "eagle-import") (part "GAS_SENSORMQ-3"))
    )
    (comp (ref "ARR1")
      (value "4_RES_ARRAY_R06031KOHM")
      (footprint "eagle-import:0603-ARC")
      (libsource (lib "eagle-import") (part "4_RES_ARRAY_R06031KOHM"))
    )
    (comp (ref "ARR2")
      (value "4_RES_ARRAY_R06031KOHM")
      (footprint "eagle-import:0603-ARC")
      (libsource (lib "eagle-import") (part "4_RES_ARRAY_R06031KOHM"))
    )
    (comp (ref "ARR3")
      (value "4_RES_ARRAY_R06031KOHM")
      (footprint "eagle-import:0603-ARC")
      (libsource (lib "eagle-import") (part "4_RES_ARRAY_R06031KOHM"))
    )
    (comp (ref "ARR4")
      (value "4_RES_ARRAY_R06031KOHM")
      (footprint "eagle-import:0603-ARC")
      (libsource (lib "eagle-import") (part "4_RES_ARRAY_R06031KOHM"))
    )
    (comp (ref "ARR5")
      (value "4_RES_ARRAY_R06031KOHM")
      (footprint "eagle-import:0603-ARC")
      (libsource (lib "eagle-import") (part "4_RES_ARRAY_R06031KOHM"))
    )
    (comp (ref "ARR6")
      (value "4_RES_ARRAY_R06031KOHM")
      (footprint "eagle-import:0603-ARC")
      (libsource (lib "eagle-import") (part "4_RES_ARRAY_R06031KOHM"))
    )
    (comp (ref "ARR7")
      (value "4_RES_ARRAY_R06031KOHM")
      (footprint "eagle-import:0603-ARC")
      (libsource (lib "eagle-import") (part "4_RES_ARRAY_R06031KOHM"))
    )
    (comp (ref "C22")
      (value "470n")
      (footprint "eagle-import:0603")
      (libsource (lib "eagle-import") (part "C0603"))
    )
    (comp (ref "C23")
      (value "1u")
      (footprint "eagle-import:0603")
      (libsource (lib "eagle-import") (part "C0603"))
    )
    (comp (ref "C24")
      (value "1u")
      (footprint "eagle-import:0603")
      (libsource (lib "eagle-import") (part "C0603"))
    )
    (comp (ref "C25")
      (value "100n")
      (footprint "eagle-import:0603")
      (libsource (lib "eagle-import") (part "C0603"))
    )
    (comp (ref "C26")
      (value "470n")
      (footprint "eagle-import:0603")
      (libsource (lib "eagle-import") (part "C0603"))
    )
    (comp (ref "C27")
      (value "470u")
      (footprint "eagle-import:D_7343-31R")
      (fields (field (name "LCSC") "C7229"))
      (libsource (lib "eagle-import") (part "C7343"))
    )
    (comp (ref "IC11")
      (value "PAM8403")
      (footprint "eagle-import:SOP-16")
      (libsource (lib "eagle-import") (part "PAM8403"))
    )
    (comp (ref "J3")
      (value "CONN_04")
      (footprint "eagle-import:1X04")
      (libsource (lib "eagle-import") (part "CONN_04"))
    )
    (comp (ref "J36")
      (value "CONN_03")
      (footprint "eagle-import:1X03")
      (libsource (lib "eagle-import") (part "CONN_03"))
    )
    (comp (ref "J37")
      (value "CONN_03")
      (footprint "eagle-import:1X03")
      (libsource (lib "eagle-import") (part "CONN_03"))
    )
    (comp (ref "J54")
      (value "CONN_02")
      (footprint "eagle-import:1X02")
      (libsource (lib "eagle-import") (part "CONN_02"))
    )
    (comp (ref "J55")
      (value "CONN_04")
      (footprint "eagle-import:1X04")
      (libsource (lib "eagle-import") (part "CONN_04"))
    )
    (comp (ref "J56")
      (value "CONN_09")
      (footprint "eagle-import:1X09")
      (libsource (lib "eagle-import") (part "CONN_09"))
    )
    (comp (ref "JACK")
      (value "AUDIO_JACK_MONO_3.5_3P")
      (footprint "eagle-import:HC-PJ-320A-3P-D")
      (libsource (lib "eagle-import") (part "AUDIO_JACK_MONO_3.5_3P"))
    )
    (comp (ref "LED4")
      (value "E6CC1205RYGC2UDA")
      (footprint "eagle-import:BICOLOR_LED")
      (libsource (lib "eagle-import") (part "RED&GREEN_LED"))
    )
    (comp (ref "LED5")
      (value "E6CC1205RYGC2UDA")
      (footprint "eagle-import:BICOLOR_LED")
      (libsource (lib "eagle-import") (part "RED&GREEN_LED"))
    )
    (comp (ref "LED6")
      (value "E6CC1205RYGC2UDA")
      (footprint "eagle-import:BICOLOR_LED")
      (libsource (lib "eagle-import") (part "RED&GREEN_LED"))
    )
    (comp (ref "LED7")
      (value "E6CC1205RYGC2UDA")
      (footprint "eagle-import:BICOLOR_LED")
      (libsource (lib "eagle-import") (part "RED&GREEN_LED"))
    )
    (comp (ref "LED8")
      (value "E6CC1205RYGC2UDA")
      (footprint "eagle-import:BICOLOR_LED")
      (libsource (lib "eagle-import") (part "RED&GREEN_LED"))
    )
    (comp (ref "LED9")
      (value "E6CC1205RYGC2UDA")
      (footprint "eagle-import:BICOLOR_LED")
      (libsource (lib "eagle-import") (part "RED&GREEN_LED"))
    )
    (comp (ref "LED10")
      (value "E6CC1205RYGC2UDA")
      (footprint "eagle-import:BICOLOR_LED")
      (libsource (lib "eagle-import") (part "RED&GREEN_LED"))
    )
    (comp (ref "LED11")
      (value "E6CC1205RYGC2UDA")
      (footprint "eagle-import:BICOLOR_LED")
      (libsource (lib "eagle-import") (part "RED&GREEN_LED"))
    )
    (comp (ref "LED12")
      (value "E6CC1205RYGC2UDA")
      (footprint "eagle-import:BICOLOR_LED")
      (libsource (lib "eagle-import") (part "RED&GREEN_LED"))
    )
    (comp (ref "PH12")
      (value "CONN_03")
      (footprint "eagle-import:1X03")
      (libsource (lib "eagle-import") (part "CONN_03"))
    )
    (comp (ref "R35")
      (value "470")
      (footprint "eagle-import:0603")
      (libsource (lib "eagle-import") (part "R0603"))
    )
    (comp (ref "R36")
      (value "470")
      (footprint "eagle-import:0603")
      (libsource (lib "eagle-import") (part "R0603"))
    )
    (comp (ref "R37")
      (value "470")
      (footprint "eagle-import:0603")
      (libsource (lib "eagle-import") (part "R0603"))
    )
    (comp (ref "R40")
      (value "10k")
      (footprint "eagle-import:0603")
      (libsource (lib "eagle-import") (part "R0603"))
    )
    (comp (ref "R41")
      (value "330")
      (footprint "eagle-import:0603")
      (libsource (lib "eagle-import") (part "R0603"))
    )
    (comp (ref "R42")
      (value "330")
      (footprint "eagle-import:0603")
      (libsource (lib "eagle-import") (part "R0603"))
    )
    (comp (ref "R43")
      (value "330")
      (footprint "eagle-import:0603")
      (libsource (lib "eagle-import") (part "R0603"))
    )
    (comp (ref "R44")
      (value "330")
      (footprint "eagle-import:0603")
      (libsource (lib "eagle-import") (part "R0603"))
    )
    (comp (ref "R45")
      (value "330")
      (footprint "eagle-import:0603")
      (libsource (lib "eagle-import") (part "R0603"))
    )
    (comp (ref "R46")
      (value "330")
      (footprint "eagle-import:0603")
      (libsource (lib "eagle-import") (part "R0603"))
    )
    (comp (ref "R47")
      (value "330")
      (footprint "eagle-import:0603")
      (libsource (lib "eagle-import") (part "R0603"))
    )
    (comp (ref "R48")
      (value "330")
      (footprint "eagle-import:0603")
      (libsource (lib "eagle-import") (part "R0603"))
    )
    (comp (ref "R49")
      (value "330")
      (footprint "eagle-import:0603")
      (libsource (lib "eagle-import") (part "R0603"))
    )
    (comp (ref "R50")
      (value "330")
      (footprint "eagle-import:0603")
      (libsource (lib "eagle-import") (part "R0603"))
    )
    (comp (ref "R51")
      (value "330")
      (footprint "eagle-import:0603")
      (libsource (lib "eagle-import") (part "R0603"))
    )
    (comp (ref "R52")
      (value "330")
      (footprint "eagle-import:0603")
      (libsource (lib "eagle-import") (part "R0603"))
    )
    (comp (ref "R53")
      (value "330")
      (footprint "eagle-import:0603")
      (libsource (lib "eagle-import") (part "R0603"))
    )
    (comp (ref "R54")
      (value "330")
      (footprint "eagle-import:0603")
      (libsource (lib "eagle-import") (part "R0603"))
    )
    (comp (ref "R55")
      (value "330")
      (footprint "eagle-import:0603")
      (libsource (lib "eagle-import") (part "R0603"))
    )
    (comp (ref "R56")
      (value "330")
      (footprint "eagle-import:0603")
      (libsource (lib "eagle-import") (part "R0603"))
    )
    (comp (ref "R57")
      (value "150")
      (footprint "eagle-import:0603")
      (libsource (lib "eagle-import") (part "R0603"))
    )
    (comp (ref "R58")
      (value "150")
      (footprint "eagle-import:0603")
      (libsource (lib "eagle-import") (part "R0603"))
    )
    (comp (ref "R59")
      (value "220")
      (footprint "eagle-import:0603")
      (libsource (lib "eagle-import") (part "R0603"))
    )
    (comp (ref "R60")
      (value "10k")
      (footprint "eagle-import:0603")
      (libsource (lib "eagle-import") (part "R0603"))
    )
    (comp (ref "RGB")
      (value "CLEAR")
      (footprint "eagle-import:LED-RGB-THRU")
      (libsource (lib "eagle-import") (part "LED-RGB-CCCLEAR"))
    )
    (comp (ref "SP1")
      (value "SPEAKERFS1508MB0810-H8.0")
      (footprint "eagle-import:FS1508MB0810-H8.0")
      (fields (field (name "MANUFACTURER") "FUET"))
      (libsource (lib "eagle-import") (part "SPEAKERFS1508MB0810-H8.0"))
    )
    (comp (ref "U$1")
      (value "FJ5101AG")
      (footprint "eagle-import:7-SEGMENT")
      (libsource (lib "eagle-import") (part "7-SEGMENT-1DIGIT-GREEN"))
    )
    (comp (ref "U$7")
      (value "CD4511BNSR")
      (footprint "eagle-import:SO16")
      (libsource (lib "eagle-import") (part "CD4511BNSR"))
    )
  )
  (nets
    (net (code "1") (name "5V") (class "Default")
      (node (ref "R38") (pin "2") (pinfunction "2_2") (pintype "passive"))
      (node (ref "S1") (pin "2") (pinfunction "LC_2") (pintype "passive"))
      (node (ref "U2") (pin "A1") (pinfunction "A1_A1") (pintype "bidirectional"))
      (node (ref "U2") (pin "HA") (pinfunction "H1_HA") (pintype "bidirectional"))
    )
    (net (code "2") (name "A1A") (class "Default")
      (node (ref "ARR1") (pin "1") (pinfunction "1_1") (pintype "passive"))
      (node (ref "IC13") (pin "1") (pinfunction "1A_1") (pintype "input"))
      (node (ref "U$2") (pin "1") (pinfunction "1_1") (pintype "passive"))
    )
    (net (code "3") (name "A1B") (class "Default")
      (node (ref "ARR1") (pin "2") (pinfunction "1_2") (pintype "passive"))
      (node (ref "IC13") (pin "2") (pinfunction "1B_2") (pintype "input"))
      (node (ref "U$2") (pin "2") (pinfunction "2_2") (pintype "passive"))
    )
    (net (code "4") (name "A1Y") (class "Default")
      (node (ref "IC13") (pin "3") (pinfunction "1Y_3") (pintype "output"))
      (node (ref "J52") (pin "1") (pinfunction "1_1") (pintype "passive"))
    )
    (net (code "5") (name "A2A") (class "Default")
      (node (ref "ARR1") (pin "3") (pinfunction "1_3") (pintype "passive"))
      (node (ref "IC13") (pin "4") (pinfunction "2A_4") (pintype "input"))
      (node (ref "U$2") (pin "3") (pinfunction "3_3") (pintype "passive"))
    )
    (net (code "6") (name "A2B") (class "Default")
      (node (ref "ARR1") (pin "4") (pinfunction "1_4") (pintype "passive"))
      (node (ref "IC13") (pin "5") (pinfunction "2B_5") (pintype "input"))
      (node (ref "U$2") (pin "4") (pinfunction "4_4") (pintype "passive"))
    )
    (net (code "7") (name "A2Y") (class "Default")
      (node (ref "IC13") (pin "6") (pinfunction "2Y_6") (pintype "output"))
      (node (ref "J52") (pin "2") (pinfunction "2_2") (pintype "passive"))
    )
    (net (code "8") (name "A3A") (class "Default")
      (node (ref "ARR2") (pin "1") (pinfunction "1_1") (pintype "passive"))
      (node (ref "IC13") (pin "9") (pinfunction "3A_9") (pintype "input"))
      (node (ref "U$2") (pin "5") (pinfunction "5_5") (pintype "passive"))
    )
    (net (code "9") (name "A3B") (class "Default")
      (node (ref "ARR2") (pin "2") (pinfunction "1_2") (pintype "passive"))
      (node (ref "IC13") (pin "10") (pinfunction "3B_10") (pintype "input"))
      (node (ref "U$2") (pin "6") (pinfunction "6_6") (pintype "passive"))
    )
    (net (code "10") (name "A3Y") (class "Default")
      (node (ref "IC13") (pin "8") (pinfunction "3Y_8") (pintype "output"))
      (node (ref "J52") (pin "3") (pinfunction "3_3") (pintype "passive"))
    )
    (net (code "11") (name "A4A") (class "Default")
      (node (ref "ARR2") (pin "3") (pinfunction "1_3") (pintype "passive"))
      (node (ref "IC13") (pin "12") (pinfunction "4A_12") (pintype "input"))
      (node (ref "U$2") (pin "7") (pinfunction "7_7") (pintype "passive"))
    )
    (net (code "12") (name "A4B") (class "Default")
      (node (ref "ARR2") (pin "4") (pinfunction "1_4") (pintype "passive"))
      (node (ref "IC13") (pin "13") (pinfunction "4B_13") (pintype "input"))
      (node (ref "U$2") (pin "8") (pinfunction "8_8") (pintype "passive"))
    )
    (net (code "13") (name "A4Y") (class "Default")
      (node (ref "IC13") (pin "11") (pinfunction "4Y_11") (pintype "output"))
      (node (ref "J52") (pin "4") (pinfunction "4_4") (pintype "passive"))
    )
    (net (code "14") (name "GND") (class "Default")
      (node (ref "ARR1") (pin "5") (pinfunction "2_5") (pintype "passive"))
      (node (ref "ARR1") (pin "6") (pinfunction "2_6") (pintype "passive"))
      (node (ref "ARR1") (pin "7") (pinfunction "2_7") (pintype "passive"))
      (node (ref "ARR1") (pin "8") (pinfunction "2_8") (pintype "passive"))
      (node (ref "ARR2") (pin "5") (pinfunction "2_5") (pintype "passive"))
      (node (ref "ARR2") (pin "6") (pinfunction "2_6") (pintype "passive"))
      (node (ref "ARR2") (pin "7") (pinfunction "2_7") (pintype "passive"))
      (node (ref "ARR2") (pin "8") (pinfunction "2_8") (pintype "passive"))
      (node (ref "ARR3") (pin "5") (pinfunction "2_5") (pintype "passive"))
      (node (ref "ARR3") (pin "6") (pinfunction "2_6") (pintype "passive"))
      (node (ref "ARR3") (pin "7") (pinfunction "2_7") (pintype "passive"))
      (node (ref "ARR3") (pin "8") (pinfunction "2_8") (pintype "passive"))
      (node (ref "ARR4") (pin "5") (pinfunction "2_5") (pintype "passive"))
      (node (ref "ARR4") (pin "6") (pinfunction "2_6") (pintype "passive"))
      (node (ref "ARR4") (pin "7") (pinfunction "2_7") (pintype "passive"))
      (node (ref "ARR4") (pin "8") (pinfunction "2_8") (pintype "passive"))
      (node (ref "ARR5") (pin "5") (pinfunction "2_5") (pintype "passive"))
      (node (ref "ARR5") (pin "6") (pinfunction "2_6") (pintype "passive"))
      (node (ref "ARR5") (pin "7") (pinfunction "2_7") (pintype "passive"))
      (node (ref "ARR5") (pin "8") (pinfunction "2_8") (pintype "passive"))
      (node (ref "ARR6") (pin "7") (pinfunction "2_7") (pintype "passive"))
      (node (ref "ARR6") (pin "8") (pinfunction "2_8") (pintype "passive"))
      (node (ref "ARR7") (pin "5") (pinfunction "2_5") (pintype "passive"))
      (node (ref "ARR7") (pin "6") (pinfunction "2_6") (pintype "passive"))
      (node (ref "ARR7") (pin "7") (pinfunction "2_7") (pintype "passive"))
      (node (ref "ARR7") (pin "8") (pinfunction "2_8") (pintype "passive"))
      (node (ref "C21") (pin "2") (pinfunction "2_2") (pintype "passive"))
      (node (ref "C23") (pin "2") (pinfunction "2_2") (pintype "passive"))
      (node (ref "C24") (pin "2") (pinfunction "2_2") (pintype "passive"))
      (node (ref "C25") (pin "2") (pinfunction "2_2") (pintype "passive"))
      (node (ref "C27") (pin "-") (pinfunction "-_-") (pintype "passive"))
      (node (ref "C28") (pin "2") (pinfunction "2_2") (pintype "passive"))
      (node (ref "C29") (pin "2") (pinfunction "2_2") (pintype "passive"))
      (node (ref "C30") (pin "2") (pinfunction "2_2") (pintype "passive"))
      (node (ref "C31") (pin "2") (pinfunction "2_2") (pintype "passive"))
      (node (ref "C32") (pin "2") (pinfunction "2_2") (pintype "passive"))
      (node (ref "C37") (pin "2") (pinfunction "2_2") (pintype "passive"))
      (node (ref "C38") (pin "2") (pinfunction "2_2") (pintype "passive"))
      (node (ref "C39") (pin "2") (pinfunction "2_2") (pintype "passive"))
      (node (ref "H1") (pin "B2,8") (pinfunction "MOUNT_B2,8") (pintype "passive"))
      (node (ref "H2") (pin "B2,8") (pinfunction "MOUNT_B2,8") (pintype "passive"))
      (node (ref "H3") (pin "B2,8") (pinfunction "MOUNT_B2,8") (pintype "passive"))
      (node (ref "H4") (pin "B2,8") (pinfunction "MOUNT_B2,8") (pintype "passive"))
      (node (ref "IC11") (pin "11") (pinfunction "GND_11") (pintype "output"))
      (node (ref "IC11") (pin "15") (pinfunction "PGND1_15") (pintype "output"))
      (node (ref "IC11") (pin "2") (pinfunction "PGND_2") (pintype "input"))
      (node (ref "IC11") (pin "9") (pinfunction "NC_9") (pintype "output"))
      (node (ref "IC13") (pin "7") (pinfunction "GND_7") (pintype "input"))
      (node (ref "IC14") (pin "7") (pinfunction "GND_7") (pintype "input"))
      (node (ref "IC15") (pin "7") (pinfunction "GND_7") (pintype "input"))
      (node (ref "IC3") (pin "11") (pinfunction "GND_11") (pintype "input"))
      (node (ref "IC4") (pin "11") (pinfunction "GND_11") (pintype "input"))
      (node (ref "IC6") (pin "8") (pinfunction "VSS_8") (pintype "power_in"))
      (node (ref "IC7") (pin "8") (pinfunction "VSS_8") (pintype "power_in"))
      (node (ref "IC8") (pin "1") (pinfunction "GND_1") (pintype "power_in"))
      (node (ref "IC9") (pin "1") (pinfunction "TEMP_1") (pintype "bidirectional"))
      (node (ref "IC9") (pin "3") (pinfunction "GND_3") (pintype "bidirectional"))
      (node (ref "J1") (pin "2") (pinfunction "-_2") (pintype "passive"))
      (node (ref "J14") (pin "1") (pinfunction "1_1") (pintype "passive"))
      (node (ref "J14") (pin "10") (pinfunction "10_10") (pintype "passive"))
      (node (ref "J14") (pin "11") (pinfunction "11_11") (pintype "passive"))
      (node (ref "J14") (pin "12") (pinfunction "12_12") (pintype "passive"))
      (node (ref "J14") (pin "13") (pinfunction "13_13") (pintype "passive"))
      (node (ref "J14") (pin "14") (pinfunction "14_14") (pintype "passive"))
      (node (ref "J14") (pin "15") (pinfunction "15_15") (pintype "passive"))
      (node (ref "J14") (pin "16") (pinfunction "16_16") (pintype "passive"))
      (node (ref "J14") (pin "17") (pinfunction "17_17") (pintype "passive"))
      (node (ref "J14") (pin "18") (pinfunction "18_18") (pintype "passive"))
      (node (ref "J14") (pin "19") (pinfunction "19_19") (pintype "passive"))
      (node (ref "J14") (pin "2") (pinfunction "2_2") (pintype "passive"))
      (node (ref "J14") (pin "20") (pinfunction "20_20") (pintype "passive"))
      (node (ref "J14") (pin "21") (pinfunction "21_21") (pintype "passive"))
      (node (ref "J14") (pin "22") (pinfunction "22_22") (pintype "passive"))
      (node (ref "J14") (pin "23") (pinfunction "23_23") (pintype "passive"))
      (node (ref "J14") (pin "24") (pinfunction "24_24") (pintype "passive"))
      (node (ref "J14") (pin "25") (pinfunction "25_25") (pintype "passive"))
      (node (ref "J14") (pin "26") (pinfunction "26_26") (pintype "passive"))
      (node (ref "J14") (pin "27") (pinfunction "27_27") (pintype "passive"))
      (node (ref "J14") (pin "28") (pinfunction "28_28") (pintype "passive"))
      (node (ref "J14") (pin "29") (pinfunction "29_29") (pintype "passive"))
      (node (ref "J14") (pin "3") (pinfunction "3_3") (pintype "passive"))
      (node (ref "J14") (pin "30") (pinfunction "30_30") (pintype "passive"))
      (node (ref "J14") (pin "4") (pinfunction "4_4") (pintype "passive"))
      (node (ref "J14") (pin "5") (pinfunction "5_5") (pintype "passive"))
      (node (ref "J14") (pin "6") (pinfunction "6_6") (pintype "passive"))
      (node (ref "J14") (pin "7") (pinfunction "7_7") (pintype "passive"))
      (node (ref "J14") (pin "8") (pinfunction "8_8") (pintype "passive"))
      (node (ref "J14") (pin "9") (pinfunction "9_9") (pintype "passive"))
      (node (ref "J36") (pin "1") (pinfunction "1_1") (pintype "passive"))
      (node (ref "LED13") (pin "1") (pinfunction "C_1") (pintype "passive"))
      (node (ref "LED2") (pin "1") (pinfunction "C_1") (pintype "passive"))
      (node (ref "LED3") (pin "1") (pinfunction "C_1") (pintype "passive"))
      (node (ref "R32") (pin "1") (pinfunction "1_1") (pintype "passive"))
      (node (ref "R35") (pin "1") (pinfunction "1_1") (pintype "passive"))
      (node (ref "R36") (pin "1") (pinfunction "1_1") (pintype "passive"))
      (node (ref "R37") (pin "1") (pinfunction "1_1") (pintype "passive"))
      (node (ref "R48") (pin "1") (pinfunction "1_1") (pintype "passive"))
      (node (ref "R49") (pin "1") (pinfunction "1_1") (pintype "passive"))
      (node (ref "R50") (pin "1") (pinfunction "1_1") (pintype "passive"))
      (node (ref "R51") (pin "1") (pinfunction "1_1") (pintype "passive"))
      (node (ref "R52") (pin "1") (pinfunction "1_1") (pintype "passive"))
      (node (ref "R53") (pin "1") (pinfunction "1_1") (pintype "passive"))
      (node (ref "R54") (pin "1") (pinfunction "1_1") (pintype "passive"))
      (node (ref "R55") (pin "1") (pinfunction "1_1") (pintype "passive"))
      (node (ref "R56") (pin "1") (pinfunction "1_1") (pintype "passive"))
      (node (ref "R67") (pin "1") (pinfunction "1_1") (pintype "passive"))
      (node (ref "RGB") (pin "C") (pinfunction "C_C") (pintype "passive"))
      (node (ref "U$1") (pin "3") (pinfunction "G1_3") (pintype "bidirectional"))
      (node (ref "U$1") (pin "8") (pinfunction "G2_8") (pintype "bidirectional"))
      (node (ref "U$7") (pin "5") (pinfunction "LE_5") (pintype "input"))
      (node (ref "U$7") (pin "8") (pinfunction "GND_8") (pintype "input"))
      (node (ref "U1") (pin "3") (pinfunction "COM_3") (pintype "bidirectional"))
      (node (ref "U1") (pin "5") (pinfunction "COM_5") (pintype "bidirectional"))
      (node (ref "U1") (pin "6") (pinfunction "COM_6") (pintype "bidirectional"))
      (node (ref "U1") (pin "7") (pinfunction "COM_7") (pintype "bidirectional"))
      (node (ref "U2") (pin "HB") (pinfunction "H2_HB") (pintype "bidirectional"))
      (node (ref "U3") (pin "1") (pinfunction "GND_1") (pintype "input"))
      (node (ref "X8") (pin "GND") (pinfunction "GND_GND") (pintype "power_in"))
    )
    (net (code "15") (name "I1A") (class "Default")
      (node (ref "ARR5") (pin "1") (pinfunction "1_1") (pintype "passive"))
      (node (ref "IC14") (pin "1") (pinfunction "1A_1") (pintype "input"))
      (node (ref "J45") (pin "1") (pinfunction "1_1") (pintype "passive"))
    )
    (net (code "16") (name "I1Y") (class "Default")
      (node (ref "IC14") (pin "2") (pinfunction "1Y_2") (pintype "output"))
      (node (ref "J46") (pin "1") (pinfunction "1_1") (pintype "passive"))
    )
    (net (code "17") (name "I2A") (class "Default")
      (node (ref "ARR5") (pin "2") (pinfunction "1_2") (pintype "passive"))
      (node (ref "IC14") (pin "3") (pinfunction "2A_3") (pintype "input"))
      (node (ref "J45") (pin "2") (pinfunction "2_2") (pintype "passive"))
    )
    (net (code "18") (name "I2Y") (class "Default")
      (node (ref "IC14") (pin "4") (pinfunction "2Y_4") (pintype "output"))
      (node (ref "J46") (pin "2") (pinfunction "2_2") (pintype "passive"))
    )
    (net (code "19") (name "I3A") (class "Default")
      (node (ref "ARR5") (pin "3") (pinfunction "1_3") (pintype "passive"))
      (node (ref "IC14") (pin "5") (pinfunction "3A_5") (pintype "input"))
      (node (ref "J45") (pin "3") (pinfunction "3_3") (pintype "passive"))
    )
    (net (code "20") (name "I3Y") (class "Default")
      (node (ref "IC14") (pin "6") (pinfunction "3Y_6") (pintype "output"))
      (node (ref "J46") (pin "3") (pinfunction "3_3") (pintype "passive"))
    )
    (net (code "21") (name "I4A") (class "Default")
      (node (ref "ARR5") (pin "4") (pinfunction "1_4") (pintype "passive"))
      (node (ref "IC14") (pin "9") (pinfunction "4A_9") (pintype "input"))
      (node (ref "J45") (pin "4") (pinfunction "4_4") (pintype "passive"))
    )
    (net (code "22") (name "I4Y") (class "Default")
      (node (ref "IC14") (pin "8") (pinfunction "4Y_8") (pintype "output"))
      (node (ref "J46") (pin "4") (pinfunction "4_4") (pintype "passive"))
    )
    (net (code "23") (name "I5A") (class "Default")
      (node (ref "ARR6") (pin "1") (pinfunction "1_1") (pintype "passive"))
      (node (ref "IC14") (pin "11") (pinfunction "5A_11") (pintype "input"))
      (node (ref "J45") (pin "5") (pinfunction "5_5") (pintype "passive"))
    )
    (net (code "24") (name "I5Y") (class "Default")
      (node (ref "IC14") (pin "10") (pinfunction "5Y_10") (pintype "output"))
      (node (ref "J46") (pin "5") (pinfunction "5_5") (pintype "passive"))
    )
    (net (code "25") (name "I6A") (class "Default")
      (node (ref "ARR6") (pin "2") (pinfunction "1_2") (pintype "passive"))
      (node (ref "IC14") (pin "13") (pinfunction "6A_13") (pintype "input"))
      (node (ref "J45") (pin "6") (pinfunction "6_6") (pintype "passive"))
    )
    (net (code "26") (name "I6Y") (class "Default")
      (node (ref "IC14") (pin "12") (pinfunction "6Y_12") (pintype "output"))
      (node (ref "J46") (pin "6") (pinfunction "6_6") (pintype "passive"))
    )
    (net (code "27") (name "IA") (class "Default")
      (node (ref "ARR7") (pin "1") (pinfunction "1_1") (pintype "passive"))
      (node (ref "J55") (pin "1") (pinfunction "1_1") (pintype "passive"))
      (node (ref "U$7") (pin "7") (pinfunction "IA_7") (pintype "input"))
    )
    (net (code "28") (name "IB") (class "Default")
      (node (ref "ARR7") (pin "2") (pinfunction "1_2") (pintype "passive"))
      (node (ref "J55") (pin "2") (pinfunction "2_2") (pintype "passive"))
      (node (ref "U$7") (pin "1") (pinfunction "IB_1") (pintype "input"))
    )
    (net (code "29") (name "IC") (class "Default")
      (node (ref "ARR7") (pin "3") (pinfunction "1_3") (pintype "passive"))
      (node (ref "J55") (pin "3") (pinfunction "3_3") (pintype "passive"))
      (node (ref "U$7") (pin "2") (pinfunction "IC_2") (pintype "input"))
    )
    (net (code "30") (name "ID") (class "Default")
      (node (ref "ARR7") (pin "4") (pinfunction "1_4") (pintype "passive"))
      (node (ref "J55") (pin "4") (pinfunction "4_4") (pintype "passive"))
      (node (ref "U$7") (pin "6") (pinfunction "ID_6") (pintype "input"))
    )
    (net (code "31") (name "INL") (class "Default")
      (node (ref "IC11") (pin "7") (pinfunction "INL_7") (pintype "input"))
      (node (ref "R60") (pin "1") (pinfunction "1_1") (pintype "passive"))
    )
    (net (code "32") (name "INR") (class "Default")
      (node (ref "IC11") (pin "10") (pinfunction "INR_10") (pintype "output"))
      (node (ref "R40") (pin "1") (pinfunction "1_1") (pintype "passive"))
    )
    (net (code "33") (name "IN_L") (class "Default")
      (node (ref "C26") (pin "1") (pinfunction "1_1") (pintype "passive"))
      (node (ref "J36") (pin "3") (pinfunction "3_3") (pintype "passive"))
    )
    (net (code "34") (name "IN_R") (class "Default")
      (node (ref "C22") (pin "1") (pinfunction "1_1") (pintype "passive"))
      (node (ref "J36") (pin "2") (pinfunction "2_2") (pintype "passive"))
    )
    (net (code "35") (name "L1") (class "Default")
      (node (ref "J56") (pin "1") (pinfunction "1_1") (pintype "passive"))
      (node (ref "LED4") (pin "2") (pinfunction "A_2") (pintype "passive"))
    )
    (net (code "36") (name "L2") (class "Default")
      (node (ref "J56") (pin "2") (pinfunction "2_2") (pintype "passive"))
      (node (ref "LED5") (pin "2") (pinfunction "A_2") (pintype "passive"))
    )
    (net (code "37") (name "L3") (class "Default")
      (node (ref "J56") (pin "3") (pinfunction "3_3") (pintype "passive"))
      (node (ref "LED6") (pin "2") (pinfunction "A_2") (pintype "passive"))
    )
    (net (code "38") (name "L4") (class "Default")
      (node (ref "J56") (pin "4") (pinfunction "4_4") (pintype "passive"))
      (node (ref "LED7") (pin "2") (pinfunction "A_2") (pintype "passive"))
      (node (ref "LED7") (pin "3") (pinfunction "A_3") (pintype "passive"))
    )
    (net (code "39") (name "L5") (class "Default")
      (node (ref "J56") (pin "5") (pinfunction "5_5") (pintype "passive"))
      (node (ref "LED8") (pin "2") (pinfunction "A_2") (pintype "passive"))
      (node (ref "LED8") (pin "3") (pinfunction "A_3") (pintype "passive"))
    )
    (net (code "40") (name "L6") (class "Default")
      (node (ref "J56") (pin "6") (pinfunction "6_6") (pintype "passive"))
      (node (ref "LED9") (pin "2") (pinfunction "A_2") (pintype "passive"))
      (node (ref "LED9") (pin "3") (pinfunction "A_3") (pintype "passive"))
    )
    (net (code "41") (name "L7") (class "Default")
      (node (ref "J56") (pin "7") (pinfunction "7_7") (pintype "passive"))
      (node (ref "LED10") (pin "3") (pinfunction "A_3") (pintype "passive"))
    )
    (net (code "42") (name "L8") (class "Default")
      (node (ref "J56") (pin "8") (pinfunction "8_8") (pintype "passive"))
      (node (ref "LED11") (pin "3") (pinfunction "A_3") (pintype "passive"))
    )
    (net (code "43") (name "L9") (class "Default")
      (node (ref "J56") (pin "9") (pinfunction "9_9") (pintype "passive"))
      (node (ref "LED12") (pin "3") (pinfunction "A_3") (pintype "passive"))
    )
    (net (code "44") (name "MUTE") (class "Default")
      (node (ref "IC11") (pin "5") (pinfunction "MUTE_5") (pintype "input"))
    )
    (net (code "45") (name "Net-(C1-Pad1)") (class "Default")
      (node (ref "C1") (pin "1") (pinfunction "1_1") (pintype "passive"))
      (node (ref "J9") (pin "1") (pinfunction "1_1") (pintype "passive"))
    )
    (net (code "46") (name "Net-(C1-Pad2)") (class "Default")
      (node (ref "C1") (pin "2") (pinfunction "2_2") (pintype "passive"))
      (node (ref "J10") (pin "1") (pinfunction "1_1") (pintype "passive"))
    )
    (net (code "47") (name "Net-(C2-Pad1)") (class "Default")
      (node (ref "C2") (pin "1") (pinfunction "1_1") (pintype "passive"))
      (node (ref "J11") (pin "1") (pinfunction "1_1") (pintype "passive"))
    )
    (net (code "48") (name "Net-(C2-Pad2)") (class "Default")
      (node (ref "C2") (pin "2") (pinfunction "2_2") (pintype "passive"))
      (node (ref "J12") (pin "1") (pinfunction "1_1") (pintype "passive"))
    )
    (net (code "49") (name "Net-(C3-Pad1)") (class "Default")
      (node (ref "C3") (pin "1") (pinfunction "1_1") (pintype "passive"))
      (node (ref "J9") (pin "2") (pinfunction "2_2") (pintype "passive"))
    )
    (net (code "50") (name "Net-(C3-Pad2)") (class "Default")
      (node (ref "C3") (pin "2") (pinfunction "2_2") (pintype "passive"))
      (node (ref "J10") (pin "2") (pinfunction "2_2") (pintype "passive"))
    )
    (net (code "51") (name "Net-(C4-Pad1)") (class "Default")
      (node (ref "C4") (pin "1") (pinfunction "1_1") (pintype "passive"))
      (node (ref "J11") (pin "2") (pinfunction "2_2") (pintype "passive"))
    )
    (net (code "52") (name "Net-(C4-Pad2)") (class "Default")
      (node (ref "C4") (pin "2") (pinfunction "2_2") (pintype "passive"))
      (node (ref "J12") (pin "2") (pinfunction "2_2") (pintype "passive"))
    )
    (net (code "53") (name "Net-(C5-Pad1)") (class "Default")
      (node (ref "C5") (pin "1") (pinfunction "1_1") (pintype "passive"))
      (node (ref "J9") (pin "3") (pinfunction "3_3") (pintype "passive"))
    )
    (net (code "54") (name "Net-(C5-Pad2)") (class "Default")
      (node (ref "C5") (pin "2") (pinfunction "2_2") (pintype "passive"))
      (node (ref "J10") (pin "3") (pinfunction "3_3") (pintype "passive"))
    )
    (net (code "55") (name "Net-(C6-Pad1)") (class "Default")
      (node (ref "C6") (pin "1") (pinfunction "1_1") (pintype "passive"))
      (node (ref "J11") (pin "3") (pinfunction "3_3") (pintype "passive"))
    )
    (net (code "56") (name "Net-(C6-Pad2)") (class "Default")
      (node (ref "C6") (pin "2") (pinfunction "2_2") (pintype "passive"))
      (node (ref "J12") (pin "3") (pinfunction "3_3") (pintype "passive"))
    )
    (net (code "57") (name "Net-(C7-Pad1)") (class "Default")
      (node (ref "C7") (pin "1") (pinfunction "1_1") (pintype "passive"))
      (node (ref "J9") (pin "4") (pinfunction "4_4") (pintype "passive"))
    )
    (net (code "58") (name "Net-(C7-Pad2)") (class "Default")
      (node (ref "C7") (pin "2") (pinfunction "2_2") (pintype "passive"))
      (node (ref "J10") (pin "4") (pinfunction "4_4") (pintype "passive"))
    )
    (net (code "59") (name "Net-(C8-Pad1)") (class "Default")
      (node (ref "C8") (pin "1") (pinfunction "1_1") (pintype "passive"))
      (node (ref "J11") (pin "4") (pinfunction "4_4") (pintype "passive"))
    )
    (net (code "60") (name "Net-(C8-Pad2)") (class "Default")
      (node (ref "C8") (pin "2") (pinfunction "2_2") (pintype "passive"))
      (node (ref "J12") (pin "4") (pinfunction "4_4") (pintype "passive"))
    )
    (net (code "61") (name "Net-(C9-Pad1)") (class "Default")
      (node (ref "C9") (pin "1") (pinfunction "1_1") (pintype "passive"))
      (node (ref "J9") (pin "5") (pinfunction "5_5") (pintype "passive"))
    )
    (net (code "62") (name "Net-(C9-Pad2)") (class "Default")
      (node (ref "C9") (pin "2") (pinfunction "2_2") (pintype "passive"))
      (node (ref "J10") (pin "5") (pinfunction "5_5") (pintype "passive"))
    )
    (net (code "63") (name "Net-(C10-Pad1)") (class "Default")
      (node (ref "C10") (pin "1") (pinfunction "1_1") (pintype "passive"))
      (node (ref "J11") (pin "5") (pinfunction "5_5") (pintype "passive"))
    )
    (net (code "64") (name "Net-(C10-Pad2)") (class "Default")
      (node (ref "C10") (pin "2") (pinfunction "2_2") (pintype "passive"))
      (node (ref "J12") (pin "5") (pinfunction "5_5") (pintype "passive"))
    )
    (net (code "65") (name "Net-(C11-Pad1)") (class "Default")
      (node (ref "C11") (pin "1") (pinfunction "1_1") (pintype "passive"))
      (node (ref "J9") (pin "6") (pinfunction "6_6") (pintype "passive"))
    )
    (net (code "66") (name "Net-(C11-Pad2)") (class "Default")
      (node (ref "C11") (pin "2") (pinfunction "2_2") (pintype "passive"))
      (node (ref "J10") (pin "6") (pinfunction "6_6") (pintype "passive"))
    )
    (net (code "67") (name "Net-(C12-Pad1)") (class "Default")
      (node (ref "C12") (pin "1") (pinfunction "1_1") (pintype "passive"))
      (node (ref "J11") (pin "6") (pinfunction "6_6") (pintype "passive"))
    )
    (net (code "68") (name "Net-(C12-Pad2)") (class "Default")
      (node (ref "C12") (pin "2") (pinfunction "2_2") (pintype "passive"))
      (node (ref "J12") (pin "6") (pinfunction "6_6") (pintype "passive"))
    )
    (net (code "69") (name "Net-(C13-Pad1)") (class "Default")
      (node (ref "C13") (pin "1") (pinfunction "1_1") (pintype "passive"))
      (node (ref "J9") (pin "7") (pinfunction "7_7") (pintype "passive"))
    )
    (net (code "70") (name "Net-(C13-Pad2)") (class "Default")
      (node (ref "C13") (pin "2") (pinfunction "2_2") (pintype "passive"))
      (node (ref "J10") (pin "7") (pinfunction "7_7") (pintype "passive"))
    )
    (net (code "71") (name "Net-(C14-Pad1)") (class "Default")
      (node (ref "C14") (pin "1") (pinfunction "1_1") (pintype "passive"))
      (node (ref "J11") (pin "7") (pinfunction "7_7") (pintype "passive"))
    )
    (net (code "72") (name "Net-(C14-Pad2)") (class "Default")
      (node (ref "C14") (pin "2") (pinfunction "2_2") (pintype "passive"))
      (node (ref "J12") (pin "7") (pinfunction "7_7") (pintype "passive"))
    )
    (net (code "73") (name "Net-(C15-Pad1)") (class "Default")
      (node (ref "C15") (pin "1") (pinfunction "1_1") (pintype "passive"))
      (node (ref "J9") (pin "8") (pinfunction "8_8") (pintype "passive"))
    )
    (net (code "74") (name "Net-(C15-Pad2)") (class "Default")
      (node (ref "C15") (pin "2") (pinfunction "2_2") (pintype "passive"))
      (node (ref "J10") (pin "8") (pinfunction "8_8") (pintype "passive"))
    )
    (net (code "75") (name "Net-(C16-Pad1)") (class "Default")
      (node (ref "C16") (pin "1") (pinfunction "1_1") (pintype "passive"))
      (node (ref "J11") (pin "8") (pinfunction "8_8") (pintype "passive"))
    )
    (net (code "76") (name "Net-(C16-Pad2)") (class "Default")
      (node (ref "C16") (pin "2") (pinfunction "2_2") (pintype "passive"))
      (node (ref "J12") (pin "8") (pinfunction "8_8") (pintype "passive"))
    )
    (net (code "77") (name "Net-(C17-Pad+)") (class "Default")
      (node (ref "C17") (pin "+") (pinfunction "+_+") (pintype "passive"))
      (node (ref "J9") (pin "9") (pinfunction "9_9") (pintype "passive"))
    )
    (net (code "78") (name "Net-(C17-Pad-)") (class "Default")
      (node (ref "C17") (pin "-") (pinfunction "-_-") (pintype "passive"))
      (node (ref "J10") (pin "9") (pinfunction "9_9") (pintype "passive"))
    )
    (net (code "79") (name "Net-(C18-Pad+)") (class "Default")
      (node (ref "C18") (pin "+") (pinfunction "+_+") (pintype "passive"))
      (node (ref "J11") (pin "9") (pinfunction "9_9") (pintype "passive"))
    )
    (net (code "80") (name "Net-(C18-Pad-)") (class "Default")
      (node (ref "C18") (pin "-") (pinfunction "-_-") (pintype "passive"))
      (node (ref "J12") (pin "9") (pinfunction "9_9") (pintype "passive"))
    )
    (net (code "81") (name "Net-(C19-Pad+)") (class "Default")
      (node (ref "C19") (pin "+") (pinfunction "+_+") (pintype "passive"))
      (node (ref "C35") (pin "+") (pinfunction "+_+") (pintype "passive"))
      (node (ref "J9") (pin "10") (pinfunction "10_10") (pintype "passive"))
    )
    (net (code "82") (name "Net-(C19-Pad-)") (class "Default")
      (node (ref "C19") (pin "-") (pinfunction "-_-") (pintype "passive"))
      (node (ref "C35") (pin "-") (pinfunction "-_-") (pintype "passive"))
      (node (ref "J10") (pin "10") (pinfunction "10_10") (pintype "passive"))
    )
    (net (code "83") (name "Net-(C20-Pad+)") (class "Default")
      (node (ref "C20") (pin "+") (pinfunction "+_+") (pintype "passive"))
      (node (ref "C36") (pin "+") (pinfunction "+_+") (pintype "passive"))
      (node (ref "J11") (pin "10") (pinfunction "10_10") (pintype "passive"))
    )
    (net (code "84") (name "Net-(C20-Pad-)") (class "Default")
      (node (ref "C20") (pin "-") (pinfunction "-_-") (pintype "passive"))
      (node (ref "C36") (pin "-") (pinfunction "-_-") (pintype "passive"))
      (node (ref "J12") (pin "10") (pinfunction "10_10") (pintype "passive"))
    )
    (net (code "85") (name "Net-(C22-Pad2)") (class "Default")
      (node (ref "C22") (pin "2") (pinfunction "2_2") (pintype "passive"))
      (node (ref "R40") (pin "2") (pinfunction "2_2") (pintype "passive"))
    )
    (net (code "86") (name "Net-(C26-Pad2)") (class "Default")
      (node (ref "C26") (pin "2") (pinfunction "2_2") (pintype "passive"))
      (node (ref "R60") (pin "2") (pinfunction "2_2") (pintype "passive"))
    )
    (net (code "87") (name "Net-(D5-PadA)") (class "Default")
      (node (ref "D5") (pin "A") (pinfunction "A_A") (pintype "passive"))
      (node (ref "J53") (pin "1") (pinfunction "1_1") (pintype "passive"))
    )
    (net (code "88") (name "Net-(D5-PadC)") (class "Default")
      (node (ref "D5") (pin "C") (pinfunction "C_C") (pintype "passive"))
      (node (ref "J44") (pin "1") (pinfunction "1_1") (pintype "passive"))
    )
    (net (code "89") (name "Net-(D6-PadA)") (class "Default")
      (node (ref "D6") (pin "A") (pinfunction "A_A") (pintype "passive"))
      (node (ref "J53") (pin "2") (pinfunction "2_2") (pintype "passive"))
    )
    (net (code "90") (name "Net-(D6-PadC)") (class "Default")
      (node (ref "D6") (pin "C") (pinfunction "C_C") (pintype "passive"))
      (node (ref "J44") (pin "2") (pinfunction "2_2") (pintype "passive"))
    )
    (net (code "91") (name "Net-(D7-PadA)") (class "Default")
      (node (ref "D7") (pin "A") (pinfunction "A_A") (pintype "passive"))
      (node (ref "J53") (pin "3") (pinfunction "3_3") (pintype "passive"))
    )
    (net (code "92") (name "Net-(D7-PadC)") (class "Default")
      (node (ref "D7") (pin "C") (pinfunction "C_C") (pintype "passive"))
      (node (ref "J44") (pin "3") (pinfunction "3_3") (pintype "passive"))
    )
    (net (code "93") (name "Net-(D8-PadA)") (class "Default")
      (node (ref "D8") (pin "A") (pinfunction "A_A") (pintype "passive"))
      (node (ref "J53") (pin "4") (pinfunction "4_4") (pintype "passive"))
    )
    (net (code "94") (name "Net-(D8-PadC)") (class "Default")
      (node (ref "D8") (pin "C") (pinfunction "C_C") (pintype "passive"))
      (node (ref "J44") (pin "4") (pinfunction "4_4") (pintype "passive"))
    )
    (net (code "95") (name "Net-(IC3-1+)") (class "Default")
      (node (ref "IC3") (pin "3") (pinfunction "1+_3") (pintype "input"))
      (node (ref "U$4") (pin "1") (pinfunction "1_1") (pintype "passive"))
    )
    (net (code "96") (name "Net-(IC3-1-)") (class "Default")
      (node (ref "IC3") (pin "2") (pinfunction "1-_2") (pintype "input"))
      (node (ref "U$4") (pin "2") (pinfunction "2_2") (pintype "passive"))
    )
    (net (code "97") (name "Net-(IC3-1Y)") (class "Default")
      (node (ref "IC3") (pin "1") (pinfunction "1Y_1") (pintype "output"))
      (node (ref "U$6") (pin "1") (pinfunction "1_1") (pintype "passive"))
    )
    (net (code "98") (name "Net-(IC3-2+)") (class "Default")
      (node (ref "IC3") (pin "5") (pinfunction "2+_5") (pintype "input"))
      (node (ref "U$4") (pin "3") (pinfunction "3_3") (pintype "passive"))
    )
    (net (code "99") (name "Net-(IC3-2-)") (class "Default")
      (node (ref "IC3") (pin "6") (pinfunction "2-_6") (pintype "input"))
      (node (ref "U$4") (pin "4") (pinfunction "4_4") (pintype "passive"))
    )
    (net (code "100") (name "Net-(IC3-2Y)") (class "Default")
      (node (ref "IC3") (pin "7") (pinfunction "2Y_7") (pintype "output"))
      (node (ref "U$6") (pin "2") (pinfunction "2_2") (pintype "passive"))
    )
    (net (code "101") (name "Net-(IC3-3+)") (class "Default")
      (node (ref "IC3") (pin "10") (pinfunction "3+_10") (pintype "input"))
      (node (ref "U$4") (pin "5") (pinfunction "5_5") (pintype "passive"))
    )
    (net (code "102") (name "Net-(IC3-3-)") (class "Default")
      (node (ref "IC3") (pin "9") (pinfunction "3-_9") (pintype "input"))
      (node (ref "U$4") (pin "6") (pinfunction "6_6") (pintype "passive"))
    )
    (net (code "103") (name "Net-(IC3-3Y)") (class "Default")
      (node (ref "IC3") (pin "8") (pinfunction "3Y_8") (pintype "output"))
      (node (ref "U$6") (pin "3") (pinfunction "3_3") (pintype "passive"))
    )
    (net (code "104") (name "Net-(IC3-4+)") (class "Default")
      (node (ref "IC3") (pin "12") (pinfunction "4+_12") (pintype "input"))
      (node (ref "U$4") (pin "7") (pinfunction "7_7") (pintype "passive"))
    )
    (net (code "105") (name "Net-(IC3-4-)") (class "Default")
      (node (ref "IC3") (pin "13") (pinfunction "4-_13") (pintype "input"))
      (node (ref "U$4") (pin "8") (pinfunction "8_8") (pintype "passive"))
    )
    (net (code "106") (name "Net-(IC3-4Y)") (class "Default")
      (node (ref "IC3") (pin "14") (pinfunction "4Y_14") (pintype "output"))
      (node (ref "U$6") (pin "4") (pinfunction "4_4") (pintype "passive"))
    )
    (net (code "107") (name "Net-(IC4-1+)") (class "Default")
      (node (ref "IC4") (pin "3") (pinfunction "1+_3") (pintype "input"))
      (node (ref "U$5") (pin "1") (pinfunction "1_1") (pintype "passive"))
    )
    (net (code "108") (name "Net-(IC4-1-)") (class "Default")
      (node (ref "IC4") (pin "2") (pinfunction "1-_2") (pintype "input"))
      (node (ref "U$5") (pin "2") (pinfunction "2_2") (pintype "passive"))
    )
    (net (code "109") (name "Net-(IC4-1Y)") (class "Default")
      (node (ref "IC4") (pin "1") (pinfunction "1Y_1") (pintype "output"))
      (node (ref "U$6") (pin "5") (pinfunction "5_5") (pintype "passive"))
    )
    (net (code "110") (name "Net-(IC4-2+)") (class "Default")
      (node (ref "IC4") (pin "5") (pinfunction "2+_5") (pintype "input"))
      (node (ref "U$5") (pin "3") (pinfunction "3_3") (pintype "passive"))
    )
    (net (code "111") (name "Net-(IC4-2-)") (class "Default")
      (node (ref "IC4") (pin "6") (pinfunction "2-_6") (pintype "input"))
      (node (ref "U$5") (pin "4") (pinfunction "4_4") (pintype "passive"))
    )
    (net (code "112") (name "Net-(IC4-2Y)") (class "Default")
      (node (ref "IC4") (pin "7") (pinfunction "2Y_7") (pintype "output"))
      (node (ref "U$6") (pin "6") (pinfunction "6_6") (pintype "passive"))
    )
    (net (code "113") (name "Net-(IC4-3+)") (class "Default")
      (node (ref "IC4") (pin "10") (pinfunction "3+_10") (pintype "input"))
      (node (ref "U$5") (pin "5") (pinfunction "5_5") (pintype "passive"))
    )
    (net (code "114") (name "Net-(IC4-3-)") (class "Default")
      (node (ref "IC4") (pin "9") (pinfunction "3-_9") (pintype "input"))
      (node (ref "U$5") (pin "6") (pinfunction "6_6") (pintype "passive"))
    )
    (net (code "115") (name "Net-(IC4-3Y)") (class "Default")
      (node (ref "IC4") (pin "8") (pinfunction "3Y_8") (pintype "output"))
      (node (ref "U$6") (pin "7") (pinfunction "7_7") (pintype "passive"))
    )
    (net (code "116") (name "Net-(IC4-4+)") (class "Default")
      (node (ref "IC4") (pin "12") (pinfunction "4+_12") (pintype "input"))
      (node (ref "U$5") (pin "7") (pinfunction "7_7") (pintype "passive"))
    )
    (net (code "117") (name "Net-(IC4-4-)") (class "Default")
      (node (ref "IC4") (pin "13") (pinfunction "4-_13") (pintype "input"))
      (node (ref "U$5") (pin "8") (pinfunction "8_8") (pintype "passive"))
    )
    (net (code "118") (name "Net-(IC4-4Y)") (class "Default")
      (node (ref "IC4") (pin "14") (pinfunction "4Y_14") (pintype "output"))
      (node (ref "U$6") (pin "8") (pinfunction "8_8") (pintype "passive"))
    )
    (net (code "119") (name "Net-(IC6A-CLK)") (class "Default")
      (node (ref "IC6") (pin "1") (pinfunction "CLK_1") (pintype "input"))
      (node (ref "J26") (pin "2") (pinfunction "2_2") (pintype "passive"))
    )
    (net (code "120") (name "Net-(IC6A-J)") (class "Default")
      (node (ref "IC6") (pin "3") (pinfunction "J_3") (pintype "input"))
      (node (ref "J26") (pin "3") (pinfunction "3_3") (pintype "passive"))
    )
    (net (code "121") (name "Net-(IC6A-K)") (class "Default")
      (node (ref "IC6") (pin "2") (pinfunction "K_2") (pintype "input"))
      (node (ref "J26") (pin "1") (pinfunction "1_1") (pintype "passive"))
    )
    (net (code "122") (name "Net-(IC6A-Q)") (class "Default")
      (node (ref "IC6") (pin "5") (pinfunction "Q_5") (pintype "output"))
      (node (ref "J47") (pin "1") (pinfunction "1_1") (pintype "passive"))
    )
    (net (code "123") (name "Net-(IC6A-~{Q})") (class "Default")
      (node (ref "IC6") (pin "6") (pinfunction "~{Q}_6") (pintype "output"))
      (node (ref "J47") (pin "2") (pinfunction "2_2") (pintype "passive"))
    )
    (net (code "124") (name "Net-(IC6B-CLK)") (class "Default")
      (node (ref "IC6") (pin "13") (pinfunction "CLK_13") (pintype "input"))
      (node (ref "J27") (pin "2") (pinfunction "2_2") (pintype "passive"))
    )
    (net (code "125") (name "Net-(IC6B-J)") (class "Default")
      (node (ref "IC6") (pin "11") (pinfunction "J_11") (pintype "input"))
      (node (ref "J27") (pin "3") (pinfunction "3_3") (pintype "passive"))
    )
    (net (code "126") (name "Net-(IC6B-K)") (class "Default")
      (node (ref "IC6") (pin "12") (pinfunction "K_12") (pintype "input"))
      (node (ref "J27") (pin "1") (pinfunction "1_1") (pintype "passive"))
    )
    (net (code "127") (name "Net-(IC6B-Q)") (class "Default")
      (node (ref "IC6") (pin "9") (pinfunction "Q_9") (pintype "output"))
      (node (ref "J48") (pin "1") (pinfunction "1_1") (pintype "passive"))
    )
    (net (code "128") (name "Net-(IC6B-~{Q})") (class "Default")
      (node (ref "IC6") (pin "7") (pinfunction "~{Q}_7") (pintype "output"))
      (node (ref "J48") (pin "2") (pinfunction "2_2") (pintype "passive"))
    )
    (net (code "129") (name "Net-(IC7A-CLK)") (class "Default")
      (node (ref "IC7") (pin "1") (pinfunction "CLK_1") (pintype "input"))
      (node (ref "J28") (pin "2") (pinfunction "2_2") (pintype "passive"))
    )
    (net (code "130") (name "Net-(IC7A-J)") (class "Default")
      (node (ref "IC7") (pin "3") (pinfunction "J_3") (pintype "input"))
      (node (ref "J28") (pin "3") (pinfunction "3_3") (pintype "passive"))
    )
    (net (code "131") (name "Net-(IC7A-K)") (class "Default")
      (node (ref "IC7") (pin "2") (pinfunction "K_2") (pintype "input"))
      (node (ref "J28") (pin "1") (pinfunction "1_1") (pintype "passive"))
    )
    (net (code "132") (name "Net-(IC7A-Q)") (class "Default")
      (node (ref "IC7") (pin "5") (pinfunction "Q_5") (pintype "output"))
      (node (ref "J49") (pin "1") (pinfunction "1_1") (pintype "passive"))
    )
    (net (code "133") (name "Net-(IC7A-~{Q})") (class "Default")
      (node (ref "IC7") (pin "6") (pinfunction "~{Q}_6") (pintype "output"))
      (node (ref "J49") (pin "2") (pinfunction "2_2") (pintype "passive"))
    )
    (net (code "134") (name "Net-(IC7B-CLK)") (class "Default")
      (node (ref "IC7") (pin "13") (pinfunction "CLK_13") (pintype "input"))
      (node (ref "J29") (pin "2") (pinfunction "2_2") (pintype "passive"))
    )
    (net (code "135") (name "Net-(IC7B-J)") (class "Default")
      (node (ref "IC7") (pin "11") (pinfunction "J_11") (pintype "input"))
      (node (ref "J29") (pin "3") (pinfunction "3_3") (pintype "passive"))
    )
    (net (code "136") (name "Net-(IC7B-K)") (class "Default")
      (node (ref "IC7") (pin "12") (pinfunction "K_12") (pintype "input"))
      (node (ref "J29") (pin "1") (pinfunction "1_1") (pintype "passive"))
    )
    (net (code "137") (name "Net-(IC7B-Q)") (class "Default")
      (node (ref "IC7") (pin "9") (pinfunction "Q_9") (pintype "output"))
      (node (ref "J50") (pin "1") (pinfunction "1_1") (pintype "passive"))
    )
    (net (code "138") (name "Net-(IC7B-~{Q})") (class "Default")
      (node (ref "IC7") (pin "7") (pinfunction "~{Q}_7") (pintype "output"))
      (node (ref "J50") (pin "2") (pinfunction "2_2") (pintype "passive"))
    )
    (net (code "139") (name "Net-(IC8-CV)") (class "Default")
      (node (ref "C21") (pin "1") (pinfunction "1_1") (pintype "passive"))
      (node (ref "IC8") (pin "5") (pinfunction "CV_5") (pintype "input"))
    )
    (net (code "140") (name "Net-(IC8-DIS)") (class "Default")
      (node (ref "IC8") (pin "7") (pinfunction "DIS_7") (pintype "input"))
      (node (ref "J30") (pin "2") (pinfunction "2_2") (pintype "passive"))
    )
    (net (code "141") (name "Net-(IC8-Q)") (class "Default")
      (node (ref "IC8") (pin "3") (pinfunction "Q_3") (pintype "output"))
      (node (ref "J51") (pin "1") (pinfunction "1_1") (pintype "passive"))
      (node (ref "R39") (pin "2") (pinfunction "2_2") (pintype "passive"))
    )
    (net (code "142") (name "Net-(IC8-THR)") (class "Default")
      (node (ref "IC8") (pin "6") (pinfunction "THR_6") (pintype "input"))
      (node (ref "J30") (pin "3") (pinfunction "3_3") (pintype "passive"))
    )
    (net (code "143") (name "Net-(IC8-TR)") (class "Default")
      (node (ref "IC8") (pin "2") (pinfunction "TR_2") (pintype "input"))
      (node (ref "J30") (pin "1") (pinfunction "1_1") (pintype "passive"))
    )
    (net (code "144") (name "Net-(IC9-PROG)") (class "Default")
      (node (ref "IC9") (pin "2") (pinfunction "PROG_2") (pintype "bidirectional"))
      (node (ref "R32") (pin "2") (pinfunction "2_2") (pintype "passive"))
    )
    (net (code "145") (name "Net-(IC9-~{CHRG})") (class "Default")
      (node (ref "IC9") (pin "7") (pinfunction "~{CHRG}_7") (pintype "bidirectional"))
      (node (ref "R33") (pin "2") (pinfunction "2_2") (pintype "passive"))
    )
    (net (code "146") (name "Net-(IC9-~{STDBY})") (class "Default")
      (node (ref "IC9") (pin "6") (pinfunction "~{STDBY}_6") (pintype "bidirectional"))
      (node (ref "R34") (pin "2") (pinfunction "2_2") (pintype "passive"))
    )
    (net (code "147") (name "Net-(J2-Pad1)") (class "Default")
      (node (ref "J2") (pin "1") (pinfunction "1_1") (pintype "passive"))
      (node (ref "R1") (pin "1") (pinfunction "1_1") (pintype "passive"))
    )
    (net (code "148") (name "Net-(J2-Pad2)") (class "Default")
      (node (ref "J2") (pin "2") (pinfunction "2_2") (pintype "passive"))
      (node (ref "R4") (pin "1") (pinfunction "1_1") (pintype "passive"))
    )
    (net (code "149") (name "Net-(J2-Pad3)") (class "Default")
      (node (ref "J2") (pin "3") (pinfunction "3_3") (pintype "passive"))
      (node (ref "R7") (pin "1") (pinfunction "1_1") (pintype "passive"))
    )
    (net (code "150") (name "Net-(J2-Pad4)") (class "Default")
      (node (ref "J2") (pin "4") (pinfunction "4_4") (pintype "passive"))
      (node (ref "R10") (pin "1") (pinfunction "1_1") (pintype "passive"))
    )
    (net (code "151") (name "Net-(J2-Pad5)") (class "Default")
      (node (ref "J2") (pin "5") (pinfunction "5_5") (pintype "passive"))
      (node (ref "R13") (pin "1") (pinfunction "1_1") (pintype "passive"))
    )
    (net (code "152") (name "Net-(J2-Pad6)") (class "Default")
      (node (ref "J2") (pin "6") (pinfunction "6_6") (pintype "passive"))
      (node (ref "R16") (pin "1") (pinfunction "1_1") (pintype "passive"))
    )
    (net (code "153") (name "Net-(J2-Pad7)") (class "Default")
      (node (ref "J2") (pin "7") (pinfunction "7_7") (pintype "passive"))
      (node (ref "R19") (pin "1") (pinfunction "1_1") (pintype "passive"))
    )
    (net (code "154") (name "Net-(J2-Pad8)") (class "Default")
      (node (ref "J2") (pin "8") (pinfunction "8_8") (pintype "passive"))
      (node (ref "R22") (pin "1") (pinfunction "1_1") (pintype "passive"))
    )
    (net (code "155") (name "Net-(J2-Pad9)") (class "Default")
      (node (ref "J2") (pin "9") (pinfunction "9_9") (pintype "passive"))
      (node (ref "R25") (pin "1") (pinfunction "1_1") (pintype "passive"))
    )
    (net (code "156") (name "Net-(J2-Pad10)") (class "Default")
      (node (ref "J2") (pin "10") (pinfunction "10_10") (pintype "passive"))
      (node (ref "R28") (pin "1") (pinfunction "1_1") (pintype "passive"))
    )
    (net (code "157") (name "Net-(J4-Pad1)") (class "Default")
      (node (ref "J4") (pin "1") (pinfunction "1_1") (pintype "passive"))
      (node (ref "R1") (pin "2") (pinfunction "2_2") (pintype "passive"))
    )
    (net (code "158") (name "Net-(J4-Pad2)") (class "Default")
      (node (ref "J4") (pin "2") (pinfunction "2_2") (pintype "passive"))
      (node (ref "R4") (pin "2") (pinfunction "2_2") (pintype "passive"))
    )
    (net (code "159") (name "Net-(J4-Pad3)") (class "Default")
      (node (ref "J4") (pin "3") (pinfunction "3_3") (pintype "passive"))
      (node (ref "R7") (pin "2") (pinfunction "2_2") (pintype "passive"))
    )
    (net (code "160") (name "Net-(J4-Pad4)") (class "Default")
      (node (ref "J4") (pin "4") (pinfunction "4_4") (pintype "passive"))
      (node (ref "R10") (pin "2") (pinfunction "2_2") (pintype "passive"))
    )
    (net (code "161") (name "Net-(J4-Pad5)") (class "Default")
      (node (ref "J4") (pin "5") (pinfunction "5_5") (pintype "passive"))
      (node (ref "R13") (pin "2") (pinfunction "2_2") (pintype "passive"))
    )
    (net (code "162") (name "Net-(J4-Pad6)") (class "Default")
      (node (ref "J4") (pin "6") (pinfunction "6_6") (pintype "passive"))
      (node (ref "R16") (pin "2") (pinfunction "2_2") (pintype "passive"))
    )
    (net (code "163") (name "Net-(J4-Pad7)") (class "Default")
      (node (ref "J4") (pin "7") (pinfunction "7_7") (pintype "passive"))
      (node (ref "R19") (pin "2") (pinfunction "2_2") (pintype "passive"))
    )
    (net (code "164") (name "Net-(J4-Pad8)") (class "Default")
      (node (ref "J4") (pin "8") (pinfunction "8_8") (pintype "passive"))
      (node (ref "R22") (pin "2") (pinfunction "2_2") (pintype "passive"))
    )
    (net (code "165") (name "Net-(J4-Pad9)") (class "Default")
      (node (ref "J4") (pin "9") (pinfunction "9_9") (pintype "passive"))
      (node (ref "R25") (pin "2") (pinfunction "2_2") (pintype "passive"))
    )
    (net (code "166") (name "Net-(J4-Pad10)") (class "Default")
      (node (ref "J4") (pin "10") (pinfunction "10_10") (pintype "passive"))
      (node (ref "R28") (pin "2") (pinfunction "2_2") (pintype "passive"))
    )
    (net (code "167") (name "Net-(J5-Pad1)") (class "Default")
      (node (ref "J5") (pin "1") (pinfunction "1_1") (pintype "passive"))
      (node (ref "R2") (pin "1") (pinfunction "1_1") (pintype "passive"))
    )
    (net (code "168") (name "Net-(J5-Pad2)") (class "Default")
      (node (ref "J5") (pin "2") (pinfunction "2_2") (pintype "passive"))
      (node (ref "R5") (pin "1") (pinfunction "1_1") (pintype "passive"))
    )
    (net (code "169") (name "Net-(J5-Pad3)") (class "Default")
      (node (ref "J5") (pin "3") (pinfunction "3_3") (pintype "passive"))
      (node (ref "R8") (pin "1") (pinfunction "1_1") (pintype "passive"))
    )
    (net (code "170") (name "Net-(J5-Pad4)") (class "Default")
      (node (ref "J5") (pin "4") (pinfunction "4_4") (pintype "passive"))
      (node (ref "R11") (pin "1") (pinfunction "1_1") (pintype "passive"))
    )
    (net (code "171") (name "Net-(J5-Pad5)") (class "Default")
      (node (ref "J5") (pin "5") (pinfunction "5_5") (pintype "passive"))
      (node (ref "R14") (pin "1") (pinfunction "1_1") (pintype "passive"))
    )
    (net (code "172") (name "Net-(J5-Pad6)") (class "Default")
      (node (ref "J5") (pin "6") (pinfunction "6_6") (pintype "passive"))
      (node (ref "R17") (pin "1") (pinfunction "1_1") (pintype "passive"))
    )
    (net (code "173") (name "Net-(J5-Pad7)") (class "Default")
      (node (ref "J5") (pin "7") (pinfunction "7_7") (pintype "passive"))
      (node (ref "R20") (pin "1") (pinfunction "1_1") (pintype "passive"))
    )
    (net (code "174") (name "Net-(J5-Pad8)") (class "Default")
      (node (ref "J5") (pin "8") (pinfunction "8_8") (pintype "passive"))
      (node (ref "R23") (pin "1") (pinfunction "1_1") (pintype "passive"))
    )
    (net (code "175") (name "Net-(J5-Pad9)") (class "Default")
      (node (ref "J5") (pin "9") (pinfunction "9_9") (pintype "passive"))
      (node (ref "R26") (pin "1") (pinfunction "1_1") (pintype "passive"))
    )
    (net (code "176") (name "Net-(J5-Pad10)") (class "Default")
      (node (ref "J5") (pin "10") (pinfunction "10_10") (pintype "passive"))
      (node (ref "R29") (pin "1") (pinfunction "1_1") (pintype "passive"))
    )
    (net (code "177") (name "Net-(J6-Pad1)") (class "Default")
      (node (ref "J6") (pin "1") (pinfunction "1_1") (pintype "passive"))
      (node (ref "R2") (pin "2") (pinfunction "2_2") (pintype "passive"))
    )
    (net (code "178") (name "Net-(J6-Pad2)") (class "Default")
      (node (ref "J6") (pin "2") (pinfunction "2_2") (pintype "passive"))
      (node (ref "R5") (pin "2") (pinfunction "2_2") (pintype "passive"))
    )
    (net (code "179") (name "Net-(J6-Pad3)") (class "Default")
      (node (ref "J6") (pin "3") (pinfunction "3_3") (pintype "passive"))
      (node (ref "R8") (pin "2") (pinfunction "2_2") (pintype "passive"))
    )
    (net (code "180") (name "Net-(J6-Pad4)") (class "Default")
      (node (ref "J6") (pin "4") (pinfunction "4_4") (pintype "passive"))
      (node (ref "R11") (pin "2") (pinfunction "2_2") (pintype "passive"))
    )
    (net (code "181") (name "Net-(J6-Pad5)") (class "Default")
      (node (ref "J6") (pin "5") (pinfunction "5_5") (pintype "passive"))
      (node (ref "R14") (pin "2") (pinfunction "2_2") (pintype "passive"))
    )
    (net (code "182") (name "Net-(J6-Pad6)") (class "Default")
      (node (ref "J6") (pin "6") (pinfunction "6_6") (pintype "passive"))
      (node (ref "R17") (pin "2") (pinfunction "2_2") (pintype "passive"))
    )
    (net (code "183") (name "Net-(J6-Pad7)") (class "Default")
      (node (ref "J6") (pin "7") (pinfunction "7_7") (pintype "passive"))
      (node (ref "R20") (pin "2") (pinfunction "2_2") (pintype "passive"))
    )
    (net (code "184") (name "Net-(J6-Pad8)") (class "Default")
      (node (ref "J6") (pin "8") (pinfunction "8_8") (pintype "passive"))
      (node (ref "R23") (pin "2") (pinfunction "2_2") (pintype "passive"))
    )
    (net (code "185") (name "Net-(J6-Pad9)") (class "Default")
      (node (ref "J6") (pin "9") (pinfunction "9_9") (pintype "passive"))
      (node (ref "R26") (pin "2") (pinfunction "2_2") (pintype "passive"))
    )
    (net (code "186") (name "Net-(J6-Pad10)") (class "Default")
      (node (ref "J6") (pin "10") (pinfunction "10_10") (pintype "passive"))
      (node (ref "R29") (pin "2") (pinfunction "2_2") (pintype "passive"))
    )
    (net (code "187") (name "Net-(J7-Pad1)") (class "Default")
      (node (ref "J7") (pin "1") (pinfunction "1_1") (pintype "passive"))
      (node (ref "R3") (pin "1") (pinfunction "1_1") (pintype "passive"))
    )
    (net (code "188") (name "Net-(J7-Pad2)") (class "Default")
      (node (ref "J7") (pin "2") (pinfunction "2_2") (pintype "passive"))
      (node (ref "R6") (pin "1") (pinfunction "1_1") (pintype "passive"))
    )
    (net (code "189") (name "Net-(J7-Pad3)") (class "Default")
      (node (ref "J7") (pin "3") (pinfunction "3_3") (pintype "passive"))
      (node (ref "R9") (pin "1") (pinfunction "1_1") (pintype "passive"))
    )
    (net (code "190") (name "Net-(J7-Pad4)") (class "Default")
      (node (ref "J7") (pin "4") (pinfunction "4_4") (pintype "passive"))
      (node (ref "R12") (pin "1") (pinfunction "1_1") (pintype "passive"))
    )
    (net (code "191") (name "Net-(J7-Pad5)") (class "Default")
      (node (ref "J7") (pin "5") (pinfunction "5_5") (pintype "passive"))
      (node (ref "R15") (pin "1") (pinfunction "1_1") (pintype "passive"))
    )
    (net (code "192") (name "Net-(J7-Pad6)") (class "Default")
      (node (ref "J7") (pin "6") (pinfunction "6_6") (pintype "passive"))
      (node (ref "R18") (pin "1") (pinfunction "1_1") (pintype "passive"))
    )
    (net (code "193") (name "Net-(J7-Pad7)") (class "Default")
      (node (ref "J7") (pin "7") (pinfunction "7_7") (pintype "passive"))
      (node (ref "R21") (pin "1") (pinfunction "1_1") (pintype "passive"))
    )
    (net (code "194") (name "Net-(J7-Pad8)") (class "Default")
      (node (ref "J7") (pin "8") (pinfunction "8_8") (pintype "passive"))
      (node (ref "R24") (pin "1") (pinfunction "1_1") (pintype "passive"))
    )
    (net (code "195") (name "Net-(J7-Pad9)") (class "Default")
      (node (ref "J7") (pin "9") (pinfunction "9_9") (pintype "passive"))
      (node (ref "R27") (pin "1") (pinfunction "1_1") (pintype "passive"))
    )
    (net (code "196") (name "Net-(J7-Pad10)") (class "Default")
      (node (ref "J7") (pin "10") (pinfunction "10_10") (pintype "passive"))
      (node (ref "R30") (pin "1") (pinfunction "1_1") (pintype "passive"))
    )
    (net (code "197") (name "Net-(J8-Pad1)") (class "Default")
      (node (ref "J8") (pin "1") (pinfunction "1_1") (pintype "passive"))
      (node (ref "R3") (pin "2") (pinfunction "2_2") (pintype "passive"))
    )
    (net (code "198") (name "Net-(J8-Pad2)") (class "Default")
      (node (ref "J8") (pin "2") (pinfunction "2_2") (pintype "passive"))
      (node (ref "R6") (pin "2") (pinfunction "2_2") (pintype "passive"))
    )
    (net (code "199") (name "Net-(J8-Pad3)") (class "Default")
      (node (ref "J8") (pin "3") (pinfunction "3_3") (pintype "passive"))
      (node (ref "R9") (pin "2") (pinfunction "2_2") (pintype "passive"))
    )
    (net (code "200") (name "Net-(J8-Pad4)") (class "Default")
      (node (ref "J8") (pin "4") (pinfunction "4_4") (pintype "passive"))
      (node (ref "R12") (pin "2") (pinfunction "2_2") (pintype "passive"))
    )
    (net (code "201") (name "Net-(J8-Pad5)") (class "Default")
      (node (ref "J8") (pin "5") (pinfunction "5_5") (pintype "passive"))
      (node (ref "R15") (pin "2") (pinfunction "2_2") (pintype "passive"))
    )
    (net (code "202") (name "Net-(J8-Pad6)") (class "Default")
      (node (ref "J8") (pin "6") (pinfunction "6_6") (pintype "passive"))
      (node (ref "R18") (pin "2") (pinfunction "2_2") (pintype "passive"))
    )
    (net (code "203") (name "Net-(J8-Pad7)") (class "Default")
      (node (ref "J8") (pin "7") (pinfunction "7_7") (pintype "passive"))
      (node (ref "R21") (pin "2") (pinfunction "2_2") (pintype "passive"))
    )
    (net (code "204") (name "Net-(J8-Pad8)") (class "Default")
      (node (ref "J8") (pin "8") (pinfunction "8_8") (pintype "passive"))
      (node (ref "R24") (pin "2") (pinfunction "2_2") (pintype "passive"))
    )
    (net (code "205") (name "Net-(J8-Pad9)") (class "Default")
      (node (ref "J8") (pin "9") (pinfunction "9_9") (pintype "passive"))
      (node (ref "R27") (pin "2") (pinfunction "2_2") (pintype "passive"))
    )
    (net (code "206") (name "Net-(J8-Pad10)") (class "Default")
      (node (ref "J8") (pin "10") (pinfunction "10_10") (pintype "passive"))
      (node (ref "R30") (pin "2") (pinfunction "2_2") (pintype "passive"))
    )
    (net (code "207") (name "Net-(J15-Pad1)") (class "Default")
      (node (ref "J15") (pin "1") (pinfunction "1_1") (pintype "passive"))
      (node (ref "J16") (pin "1") (pinfunction "1_1") (pintype "passive"))
      (node (ref "J17") (pin "1") (pinfunction "1_1") (pintype "passive"))
      (node (ref "J18") (pin "1") (pinfunction "1_1") (pintype "passive"))
    )
    (net (code "208") (name "Net-(J15-Pad2)") (class "Default")
      (node (ref "J15") (pin "2") (pinfunction "2_2") (pintype "passive"))
      (node (ref "J16") (pin "2") (pinfunction "2_2") (pintype "passive"))
      (node (ref "J17") (pin "2") (pinfunction "2_2") (pintype "passive"))
      (node (ref "J18") (pin "2") (pinfunction "2_2") (pintype "passive"))
    )
    (net (code "209") (name "Net-(J15-Pad3)") (class "Default")
      (node (ref "J15") (pin "3") (pinfunction "3_3") (pintype "passive"))
      (node (ref "J16") (pin "3") (pinfunction "3_3") (pintype "passive"))
      (node (ref "J17") (pin "3") (pinfunction "3_3") (pintype "passive"))
      (node (ref "J18") (pin "3") (pinfunction "3_3") (pintype "passive"))
    )
    (net (code "210") (name "Net-(J15-Pad4)") (class "Default")
      (node (ref "J15") (pin "4") (pinfunction "4_4") (pintype "passive"))
      (node (ref "J16") (pin "4") (pinfunction "4_4") (pintype "passive"))
      (node (ref "J17") (pin "4") (pinfunction "4_4") (pintype "passive"))
      (node (ref "J18") (pin "4") (pinfunction "4_4") (pintype "passive"))
    )
    (net (code "211") (name "Net-(J15-Pad5)") (class "Default")
      (node (ref "J15") (pin "5") (pinfunction "5_5") (pintype "passive"))
      (node (ref "J16") (pin "5") (pinfunction "5_5") (pintype "passive"))
      (node (ref "J17") (pin "5") (pinfunction "5_5") (pintype "passive"))
      (node (ref "J18") (pin "5") (pinfunction "5_5") (pintype "passive"))
    )
    (net (code "212") (name "Net-(J15-Pad6)") (class "Default")
      (node (ref "J15") (pin "6") (pinfunction "6_6") (pintype "passive"))
      (node (ref "J16") (pin "6") (pinfunction "6_6") (pintype "passive"))
      (node (ref "J17") (pin "6") (pinfunction "6_6") (pintype "passive"))
      (node (ref "J18") (pin "6") (pinfunction "6_6") (pintype "passive"))
    )
    (net (code "213") (name "Net-(J15-Pad7)") (class "Default")
      (node (ref "J15") (pin "7") (pinfunction "7_7") (pintype "passive"))
      (node (ref "J16") (pin "7") (pinfunction "7_7") (pintype "passive"))
      (node (ref "J17") (pin "7") (pinfunction "7_7") (pintype "passive"))
      (node (ref "J18") (pin "7") (pinfunction "7_7") (pintype "passive"))
    )
    (net (code "214") (name "Net-(J15-Pad8)") (class "Default")
      (node (ref "J15") (pin "8") (pinfunction "8_8") (pintype "passive"))
      (node (ref "J16") (pin "8") (pinfunction "8_8") (pintype "passive"))
      (node (ref "J17") (pin "8") (pinfunction "8_8") (pintype "passive"))
      (node (ref "J18") (pin "8") (pinfunction "8_8") (pintype "passive"))
    )
    (net (code "215") (name "Net-(J15-Pad9)") (class "Default")
      (node (ref "J15") (pin "9") (pinfunction "9_9") (pintype "passive"))
      (node (ref "J16") (pin "9") (pinfunction "9_9") (pintype "passive"))
      (node (ref "J17") (pin "9") (pinfunction "9_9") (pintype "passive"))
      (node (ref "J18") (pin "9") (pinfunction "9_9") (pintype "passive"))
    )
    (net (code "216") (name "Net-(J15-Pad10)") (class "Default")
      (node (ref "J15") (pin "10") (pinfunction "10_10") (pintype "passive"))
      (node (ref "J16") (pin "10") (pinfunction "10_10") (pintype "passive"))
      (node (ref "J17") (pin "10") (pinfunction "10_10") (pintype "passive"))
      (node (ref "J18") (pin "10") (pinfunction "10_10") (pintype "passive"))
    )
    (net (code "217") (name "Net-(J15-Pad11)") (class "Default")
      (node (ref "J15") (pin "11") (pinfunction "11_11") (pintype "passive"))
      (node (ref "J16") (pin "11") (pinfunction "11_11") (pintype "passive"))
      (node (ref "J17") (pin "11") (pinfunction "11_11") (pintype "passive"))
      (node (ref "J18") (pin "11") (pinfunction "11_11") (pintype "passive"))
    )
    (net (code "218") (name "Net-(J15-Pad12)") (class "Default")
      (node (ref "J15") (pin "12") (pinfunction "12_12") (pintype "passive"))
      (node (ref "J16") (pin "12") (pinfunction "12_12") (pintype "passive"))
      (node (ref "J17") (pin "12") (pinfunction "12_12") (pintype "passive"))
      (node (ref "J18") (pin "12") (pinfunction "12_12") (pintype "passive"))
    )
    (net (code "219") (name "Net-(J15-Pad13)") (class "Default")
      (node (ref "J15") (pin "13") (pinfunction "13_13") (pintype "passive"))
      (node (ref "J16") (pin "13") (pinfunction "13_13") (pintype "passive"))
      (node (ref "J17") (pin "13") (pinfunction "13_13") (pintype "passive"))
      (node (ref "J18") (pin "13") (pinfunction "13_13") (pintype "passive"))
    )
    (net (code "220") (name "Net-(J15-Pad14)") (class "Default")
      (node (ref "J15") (pin "14") (pinfunction "14_14") (pintype "passive"))
      (node (ref "J16") (pin "14") (pinfunction "14_14") (pintype "passive"))
      (node (ref "J17") (pin "14") (pinfunction "14_14") (pintype "passive"))
      (node (ref "J18") (pin "14") (pinfunction "14_14") (pintype "passive"))
    )
    (net (code "221") (name "Net-(J15-Pad15)") (class "Default")
      (node (ref "J15") (pin "15") (pinfunction "15_15") (pintype "passive"))
      (node (ref "J16") (pin "15") (pinfunction "15_15") (pintype "passive"))
      (node (ref "J17") (pin "15") (pinfunction "15_15") (pintype "passive"))
      (node (ref "J18") (pin "15") (pinfunction "15_15") (pintype "passive"))
    )
    (net (code "222") (name "Net-(J15-Pad16)") (class "Default")
      (node (ref "J15") (pin "16") (pinfunction "16_16") (pintype "passive"))
      (node (ref "J16") (pin "16") (pinfunction "16_16") (pintype "passive"))
      (node (ref "J17") (pin "16") (pinfunction "16_16") (pintype "passive"))
      (node (ref "J18") (pin "16") (pinfunction "16_16") (pintype "passive"))
    )
    (net (code "223") (name "Net-(J15-Pad17)") (class "Default")
      (node (ref "J15") (pin "17") (pinfunction "17_17") (pintype "passive"))
      (node (ref "J16") (pin "17") (pinfunction "17_17") (pintype "passive"))
      (node (ref "J17") (pin "17") (pinfunction "17_17") (pintype "passive"))
      (node (ref "J18") (pin "17") (pinfunction "17_17") (pintype "passive"))
    )
    (net (code "224") (name "Net-(J15-Pad18)") (class "Default")
      (node (ref "J15") (pin "18") (pinfunction "18_18") (pintype "passive"))
      (node (ref "J16") (pin "18") (pinfunction "18_18") (pintype "passive"))
      (node (ref "J17") (pin "18") (pinfunction "18_18") (pintype "passive"))
      (node (ref "J18") (pin "18") (pinfunction "18_18") (pintype "passive"))
    )
    (net (code "225") (name "Net-(J15-Pad19)") (class "Default")
      (node (ref "J15") (pin "19") (pinfunction "19_19") (pintype "passive"))
      (node (ref "J16") (pin "19") (pinfunction "19_19") (pintype "passive"))
      (node (ref "J17") (pin "19") (pinfunction "19_19") (pintype "passive"))
      (node (ref "J18") (pin "19") (pinfunction "19_19") (pintype "passive"))
    )
    (net (code "226") (name "Net-(J15-Pad20)") (class "Default")
      (node (ref "J15") (pin "20") (pinfunction "20_20") (pintype "passive"))
      (node (ref "J16") (pin "20") (pinfunction "20_20") (pintype "passive"))
      (node (ref "J17") (pin "20") (pinfunction "20_20") (pintype "passive"))
      (node (ref "J18") (pin "20") (pinfunction "20_20") (pintype "passive"))
    )
    (net (code "227") (name "Net-(J15-Pad21)") (class "Default")
      (node (ref "J15") (pin "21") (pinfunction "21_21") (pintype "passive"))
      (node (ref "J16") (pin "21") (pinfunction "21_21") (pintype "passive"))
      (node (ref "J17") (pin "21") (pinfunction "21_21") (pintype "passive"))
      (node (ref "J18") (pin "21") (pinfunction "21_21") (pintype "passive"))
    )
    (net (code "228") (name "Net-(J15-Pad22)") (class "Default")
      (node (ref "J15") (pin "22") (pinfunction "22_22") (pintype "passive"))
      (node (ref "J16") (pin "22") (pinfunction "22_22") (pintype "passive"))
      (node (ref "J17") (pin "22") (pinfunction "22_22") (pintype "passive"))
      (node (ref "J18") (pin "22") (pinfunction "22_22") (pintype "passive"))
    )
    (net (code "229") (name "Net-(J15-Pad23)") (class "Default")
      (node (ref "J15") (pin "23") (pinfunction "23_23") (pintype "passive"))
      (node (ref "J16") (pin "23") (pinfunction "23_23") (pintype "passive"))
      (node (ref "J17") (pin "23") (pinfunction "23_23") (pintype "passive"))
      (node (ref "J18") (pin "23") (pinfunction "23_23") (pintype "passive"))
    )
    (net (code "230") (name "Net-(J15-Pad24)") (class "Default")
      (node (ref "J15") (pin "24") (pinfunction "24_24") (pintype "passive"))
      (node (ref "J16") (pin "24") (pinfunction "24_24") (pintype "passive"))
      (node (ref "J17") (pin "24") (pinfunction "24_24") (pintype "passive"))
      (node (ref "J18") (pin "24") (pinfunction "24_24") (pintype "passive"))
    )
    (net (code "231") (name "Net-(J15-Pad25)") (class "Default")
      (node (ref "J15") (pin "25") (pinfunction "25_25") (pintype "passive"))
      (node (ref "J16") (pin "25") (pinfunction "25_25") (pintype "passive"))
      (node (ref "J17") (pin "25") (pinfunction "25_25") (pintype "passive"))
      (node (ref "J18") (pin "25") (pinfunction "25_25") (pintype "passive"))
    )
    (net (code "232") (name "Net-(J15-Pad26)") (class "Default")
      (node (ref "J15") (pin "26") (pinfunction "26_26") (pintype "passive"))
      (node (ref "J16") (pin "26") (pinfunction "26_26") (pintype "passive"))
      (node (ref "J17") (pin "26") (pinfunction "26_26") (pintype "passive"))
      (node (ref "J18") (pin "26") (pinfunction "26_26") (pintype "passive"))
    )
    (net (code "233") (name "Net-(J15-Pad27)") (class "Default")
      (node (ref "J15") (pin "27") (pinfunction "27_27") (pintype "passive"))
      (node (ref "J16") (pin "27") (pinfunction "27_27") (pintype "passive"))
      (node (ref "J17") (pin "27") (pinfunction "27_27") (pintype "passive"))
      (node (ref "J18") (pin "27") (pinfunction "27_27") (pintype "passive"))
    )
    (net (code "234") (name "Net-(J15-Pad28)") (class "Default")
      (node (ref "J15") (pin "28") (pinfunction "28_28") (pintype "passive"))
      (node (ref "J16") (pin "28") (pinfunction "28_28") (pintype "passive"))
      (node (ref "J17") (pin "28") (pinfunction "28_28") (pintype "passive"))
      (node (ref "J18") (pin "28") (pinfunction "28_28") (pintype "passive"))
    )
    (net (code "235") (name "Net-(J15-Pad29)") (class "Default")
      (node (ref "J15") (pin "29") (pinfunction "29_29") (pintype "passive"))
      (node (ref "J16") (pin "29") (pinfunction "29_29") (pintype "passive"))
      (node (ref "J17") (pin "29") (pinfunction "29_29") (pintype "passive"))
      (node (ref "J18") (pin "29") (pinfunction "29_29") (pintype "passive"))
    )
    (net (code "236") (name "Net-(J15-Pad30)") (class "Default")
      (node (ref "J15") (pin "30") (pinfunction "30_30") (pintype "passive"))
      (node (ref "J16") (pin "30") (pinfunction "30_30") (pintype "passive"))
      (node (ref "J17") (pin "30") (pinfunction "30_30") (pintype "passive"))
      (node (ref "J18") (pin "30") (pinfunction "30_30") (pintype "passive"))
    )
    (net (code "237") (name "Net-(J20-Pad1)") (class "Default")
      (node (ref "J20") (pin "1") (pinfunction "1_1") (pintype "passive"))
      (node (ref "S10") (pin "1") (pinfunction "1_1") (pintype "passive"))
      (node (ref "S8") (pin "1") (pinfunction "1_1") (pintype "passive"))
      (node (ref "S9") (pin "1") (pinfunction "1_1") (pintype "passive"))
    )
    (net (code "238") (name "Net-(J20-Pad2)") (class "Default")
      (node (ref "J20") (pin "2") (pinfunction "2_2") (pintype "passive"))
      (node (ref "S5") (pin "1") (pinfunction "1_1") (pintype "passive"))
      (node (ref "S6") (pin "1") (pinfunction "1_1") (pintype "passive"))
      (node (ref "S7") (pin "1") (pinfunction "1_1") (pintype "passive"))
    )
    (net (code "239") (name "Net-(J20-Pad3)") (class "Default")
      (node (ref "J20") (pin "3") (pinfunction "3_3") (pintype "passive"))
      (node (ref "S2") (pin "1") (pinfunction "1_1") (pintype "passive"))
      (node (ref "S3") (pin "1") (pinfunction "1_1") (pintype "passive"))
      (node (ref "S4") (pin "1") (pinfunction "1_1") (pintype "passive"))
    )
    (net (code "240") (name "Net-(J22-Pad1)") (class "Default")
      (node (ref "J22") (pin "1") (pinfunction "1_1") (pintype "passive"))
      (node (ref "P1") (pin "3") (pinfunction "3_3") (pintype "passive"))
    )
    (net (code "241") (name "Net-(J22-Pad2)") (class "Default")
      (node (ref "J22") (pin "2") (pinfunction "2_2") (pintype "passive"))
      (node (ref "P1") (pin "2") (pinfunction "2_2") (pintype "passive"))
    )
    (net (code "242") (name "Net-(J22-Pad3)") (class "Default")
      (node (ref "J22") (pin "3") (pinfunction "3_3") (pintype "passive"))
      (node (ref "P1") (pin "1") (pinfunction "1_1") (pintype "passive"))
    )
    (net (code "243") (name "Net-(J23-Pad1)") (class "Default")
      (node (ref "J23") (pin "1") (pinfunction "1_1") (pintype "passive"))
      (node (ref "P2") (pin "3") (pinfunction "3_3") (pintype "passive"))
    )
    (net (code "244") (name "Net-(J23-Pad2)") (class "Default")
      (node (ref "J23") (pin "2") (pinfunction "2_2") (pintype "passive"))
      (node (ref "P2") (pin "2") (pinfunction "2_2") (pintype "passive"))
    )
    (net (code "245") (name "Net-(J23-Pad3)") (class "Default")
      (node (ref "J23") (pin "3") (pinfunction "3_3") (pintype "passive"))
      (node (ref "P2") (pin "1") (pinfunction "1_1") (pintype "passive"))
    )
    (net (code "246") (name "Net-(J24-Pad1)") (class "Default")
      (node (ref "J24") (pin "1") (pinfunction "1_1") (pintype "passive"))
      (node (ref "P3") (pin "3") (pinfunction "3_3") (pintype "passive"))
    )
    (net (code "247") (name "Net-(J24-Pad2)") (class "Default")
      (node (ref "J24") (pin "2") (pinfunction "2_2") (pintype "passive"))
      (node (ref "P3") (pin "2") (pinfunction "2_2") (pintype "passive"))
    )
    (net (code "248") (name "Net-(J24-Pad3)") (class "Default")
      (node (ref "J24") (pin "3") (pinfunction "3_3") (pintype "passive"))
      (node (ref "P3") (pin "1") (pinfunction "1_1") (pintype "passive"))
    )
    (net (code "249") (name "Net-(J37-Pad1)") (class "Default")
      (node (ref "J37") (pin "1") (pinfunction "1_1") (pintype "passive"))
      (node (ref "R57") (pin "2") (pinfunction "2_2") (pintype "passive"))
    )
    (net (code "250") (name "Net-(J37-Pad2)") (class "Default")
      (node (ref "J37") (pin "2") (pinfunction "2_2") (pintype "passive"))
      (node (ref "R58") (pin "2") (pinfunction "2_2") (pintype "passive"))
    )
    (net (code "251") (name "Net-(J37-Pad3)") (class "Default")
      (node (ref "J37") (pin "3") (pinfunction "3_3") (pintype "passive"))
      (node (ref "R59") (pin "2") (pinfunction "2_2") (pintype "passive"))
    )
    (net (code "252") (name "Net-(J38-Pad1)") (class "Default")
      (node (ref "J38") (pin "1") (pinfunction "1_1") (pintype "passive"))
      (node (ref "MIC") (pin "2") (pinfunction "2_2") (pintype "passive"))
    )
    (net (code "253") (name "Net-(J38-Pad2)") (class "Default")
      (node (ref "J38") (pin "2") (pinfunction "2_2") (pintype "passive"))
      (node (ref "MIC") (pin "1") (pinfunction "1_1") (pintype "passive"))
    )
    (net (code "254") (name "Net-(J39-Pad1)") (class "Default")
      (node (ref "J39") (pin "1") (pinfunction "1_1") (pintype "passive"))
      (node (ref "PH1") (pin "1") (pinfunction "1_1") (pintype "passive"))
    )
    (net (code "255") (name "Net-(J39-Pad2)") (class "Default")
      (node (ref "J39") (pin "2") (pinfunction "2_2") (pintype "passive"))
      (node (ref "PH1") (pin "3") (pinfunction "3_3") (pintype "passive"))
    )
    (net (code "256") (name "Net-(J40-Pad1)") (class "Default")
      (node (ref "J40") (pin "1") (pinfunction "1_1") (pintype "passive"))
      (node (ref "NTC") (pin "2") (pinfunction "2_2") (pintype "passive"))
    )
    (net (code "257") (name "Net-(J40-Pad2)") (class "Default")
      (node (ref "J40") (pin "2") (pinfunction "2_2") (pintype "passive"))
      (node (ref "NTC") (pin "1") (pinfunction "1_1") (pintype "passive"))
    )
    (net (code "258") (name "Net-(J41-Pad1)") (class "Default")
      (node (ref "J41") (pin "1") (pinfunction "1_1") (pintype "passive"))
      (node (ref "U$16") (pin "1") (pinfunction "1_1") (pintype "bidirectional"))
    )
    (net (code "259") (name "Net-(J41-Pad2)") (class "Default")
      (node (ref "J41") (pin "2") (pinfunction "2_2") (pintype "passive"))
      (node (ref "U$16") (pin "0") (pinfunction "0_0") (pintype "bidirectional"))
    )
    (net (code "260") (name "Net-(J42-Pad1)") (class "Default")
      (node (ref "J42") (pin "1") (pinfunction "1_1") (pintype "passive"))
      (node (ref "R67") (pin "2") (pinfunction "2_2") (pintype "passive"))
      (node (ref "U2") (pin "B1") (pinfunction "B1_B1") (pintype "bidirectional"))
    )
    (net (code "261") (name "Net-(J54-Pad1)") (class "Default")
      (node (ref "J54") (pin "1") (pinfunction "1_1") (pintype "passive"))
      (node (ref "SP1") (pin "-") (pinfunction "-_-") (pintype "bidirectional"))
    )
    (net (code "262") (name "Net-(J54-Pad2)") (class "Default")
      (node (ref "J54") (pin "2") (pinfunction "2_2") (pintype "passive"))
      (node (ref "SP1") (pin "+") (pinfunction "+_+") (pintype "bidirectional"))
    )
    (net (code "263") (name "Net-(JACK-Pad1)") (class "Default")
      (node (ref "JACK") (pin "1") (pinfunction "1_1") (pintype "bidirectional"))
      (node (ref "PH12") (pin "1") (pinfunction "1_1") (pintype "passive"))
    )
    (net (code "264") (name "Net-(JACK-Pad2)") (class "Default")
      (node (ref "JACK") (pin "2") (pinfunction "2_2") (pintype "bidirectional"))
      (node (ref "PH12") (pin "2") (pinfunction "2_2") (pintype "passive"))
    )
    (net (code "265") (name "Net-(JACK-Pad3)") (class "Default")
      (node (ref "JACK") (pin "3") (pinfunction "3_3") (pintype "bidirectional"))
      (node (ref "PH12") (pin "3") (pinfunction "3_3") (pintype "passive"))
    )
    (net (code "266") (name "Net-(LED1A-C)") (class "Default")
      (node (ref "LED1") (pin "1") (pinfunction "C_1") (pintype "passive"))
      (node (ref "R34") (pin "1") (pinfunction "1_1") (pintype "passive"))
    )
    (net (code "267") (name "Net-(LED1B-C)") (class "Default")
      (node (ref "LED1") (pin "4") (pinfunction "C_4") (pintype "passive"))
      (node (ref "R33") (pin "1") (pinfunction "1_1") (pintype "passive"))
    )
    (net (code "268") (name "Net-(LED2A-A)") (class "Default")
      (node (ref "LED2") (pin "2") (pinfunction "A_2") (pintype "passive"))
      (node (ref "R31") (pin "2") (pinfunction "2_2") (pintype "passive"))
    )
    (net (code "269") (name "Net-(LED3A-A)") (class "Default")
      (node (ref "LED3") (pin "2") (pinfunction "A_2") (pintype "passive"))
      (node (ref "R39") (pin "1") (pinfunction "1_1") (pintype "passive"))
    )
    (net (code "270") (name "Net-(LED4A-C)") (class "Default")
      (node (ref "LED4") (pin "1") (pinfunction "C_1") (pintype "passive"))
      (node (ref "R48") (pin "2") (pinfunction "2_2") (pintype "passive"))
    )
    (net (code "271") (name "Net-(LED5A-C)") (class "Default")
      (node (ref "LED5") (pin "1") (pinfunction "C_1") (pintype "passive"))
      (node (ref "R49") (pin "2") (pinfunction "2_2") (pintype "passive"))
    )
    (net (code "272") (name "Net-(LED6A-C)") (class "Default")
      (node (ref "LED6") (pin "1") (pinfunction "C_1") (pintype "passive"))
      (node (ref "R50") (pin "2") (pinfunction "2_2") (pintype "passive"))
    )
    (net (code "273") (name "Net-(LED7A-C)") (class "Default")
      (node (ref "LED7") (pin "1") (pinfunction "C_1") (pintype "passive"))
      (node (ref "R51") (pin "2") (pinfunction "2_2") (pintype "passive"))
    )
    (net (code "274") (name "Net-(LED7B-C)") (class "Default")
      (node (ref "LED7") (pin "4") (pinfunction "C_4") (pintype "passive"))
      (node (ref "R35") (pin "2") (pinfunction "2_2") (pintype "passive"))
    )
    (net (code "275") (name "Net-(LED8A-C)") (class "Default")
      (node (ref "LED8") (pin "1") (pinfunction "C_1") (pintype "passive"))
      (node (ref "R52") (pin "2") (pinfunction "2_2") (pintype "passive"))
    )
    (net (code "276") (name "Net-(LED8B-C)") (class "Default")
      (node (ref "LED8") (pin "4") (pinfunction "C_4") (pintype "passive"))
      (node (ref "R36") (pin "2") (pinfunction "2_2") (pintype "passive"))
    )
    (net (code "277") (name "Net-(LED9A-C)") (class "Default")
      (node (ref "LED9") (pin "1") (pinfunction "C_1") (pintype "passive"))
      (node (ref "R53") (pin "2") (pinfunction "2_2") (pintype "passive"))
    )
    (net (code "278") (name "Net-(LED9B-C)") (class "Default")
      (node (ref "LED9") (pin "4") (pinfunction "C_4") (pintype "passive"))
      (node (ref "R37") (pin "2") (pinfunction "2_2") (pintype "passive"))
    )
    (net (code "279") (name "Net-(LED10B-C)") (class "Default")
      (node (ref "LED10") (pin "4") (pinfunction "C_4") (pintype "passive"))
      (node (ref "R54") (pin "2") (pinfunction "2_2") (pintype "passive"))
    )
    (net (code "280") (name "Net-(LED11B-C)") (class "Default")
      (node (ref "LED11") (pin "4") (pinfunction "C_4") (pintype "passive"))
      (node (ref "R55") (pin "2") (pinfunction "2_2") (pintype "passive"))
    )
    (net (code "281") (name "Net-(LED12B-C)") (class "Default")
      (node (ref "LED12") (pin "4") (pinfunction "C_4") (pintype "passive"))
      (node (ref "R56") (pin "2") (pinfunction "2_2") (pintype "passive"))
    )
    (net (code "282") (name "Net-(LED13A-A)") (class "Default")
      (node (ref "LED13") (pin "2") (pinfunction "A_2") (pintype "passive"))
      (node (ref "R38") (pin "1") (pinfunction "1_1") (pintype "passive"))
    )
    (net (code "283") (name "Net-(R57-Pad1)") (class "Default")
      (node (ref "R57") (pin "1") (pinfunction "1_1") (pintype "passive"))
      (node (ref "RGB") (pin "R") (pinfunction "R_R") (pintype "passive"))
    )
    (net (code "284") (name "Net-(R58-Pad1)") (class "Default")
      (node (ref "R58") (pin "1") (pinfunction "1_1") (pintype "passive"))
      (node (ref "RGB") (pin "G") (pinfunction "G_G") (pintype "passive"))
    )
    (net (code "285") (name "Net-(R59-Pad1)") (class "Default")
      (node (ref "R59") (pin "1") (pinfunction "1_1") (pintype "passive"))
      (node (ref "RGB") (pin "B") (pinfunction "B_B") (pintype "passive"))
    )
    (net (code "286") (name "Net-(S1-RC)") (class "Default")
      (node (ref "C38") (pin "1") (pinfunction "1_1") (pintype "passive"))
      (node (ref "S1") (pin "5") (pinfunction "RC_5") (pintype "passive"))
      (node (ref "U3") (pin "3") (pinfunction "IN_3") (pintype "input"))
    )
    (net (code "287") (name "Net-(S2-2)") (class "Default")
      (node (ref "J21") (pin "1") (pinfunction "1_1") (pintype "passive"))
      (node (ref "S2") (pin "3") (pinfunction "2_3") (pintype "passive"))
      (node (ref "S5") (pin "3") (pinfunction "2_3") (pintype "passive"))
      (node (ref "S8") (pin "3") (pinfunction "2_3") (pintype "passive"))
    )
    (net (code "288") (name "Net-(S3-2)") (class "Default")
      (node (ref "J21") (pin "2") (pinfunction "2_2") (pintype "passive"))
      (node (ref "S3") (pin "3") (pinfunction "2_3") (pintype "passive"))
      (node (ref "S6") (pin "3") (pinfunction "2_3") (pintype "passive"))
      (node (ref "S9") (pin "3") (pinfunction "2_3") (pintype "passive"))
    )
    (net (code "289") (name "Net-(S10-2)") (class "Default")
      (node (ref "J21") (pin "3") (pinfunction "3_3") (pintype "passive"))
      (node (ref "S10") (pin "3") (pinfunction "2_3") (pintype "passive"))
      (node (ref "S4") (pin "3") (pinfunction "2_3") (pintype "passive"))
      (node (ref "S7") (pin "3") (pinfunction "2_3") (pintype "passive"))
    )
    (net (code "290") (name "Net-(T1-B)") (class "Default")
      (node (ref "J31") (pin "2") (pinfunction "2_2") (pintype "passive"))
      (node (ref "T1") (pin "1") (pinfunction "B_1") (pintype "passive"))
    )
    (net (code "291") (name "Net-(T1-C)") (class "Default")
      (node (ref "J31") (pin "3") (pinfunction "3_3") (pintype "passive"))
      (node (ref "T1") (pin "3") (pinfunction "C_3") (pintype "passive"))
    )
    (net (code "292") (name "Net-(T1-E)") (class "Default")
      (node (ref "J31") (pin "1") (pinfunction "1_1") (pintype "passive"))
      (node (ref "T1") (pin "2") (pinfunction "E_2") (pintype "passive"))
    )
    (net (code "293") (name "Net-(T2-B)") (class "Default")
      (node (ref "J32") (pin "2") (pinfunction "2_2") (pintype "passive"))
      (node (ref "T2") (pin "1") (pinfunction "B_1") (pintype "passive"))
    )
    (net (code "294") (name "Net-(T2-C)") (class "Default")
      (node (ref "J32") (pin "3") (pinfunction "3_3") (pintype "passive"))
      (node (ref "T2") (pin "3") (pinfunction "C_3") (pintype "passive"))
    )
    (net (code "295") (name "Net-(T2-E)") (class "Default")
      (node (ref "J32") (pin "1") (pinfunction "1_1") (pintype "passive"))
      (node (ref "T2") (pin "2") (pinfunction "E_2") (pintype "passive"))
    )
    (net (code "296") (name "Net-(T3-B)") (class "Default")
      (node (ref "J33") (pin "2") (pinfunction "2_2") (pintype "passive"))
      (node (ref "T3") (pin "1") (pinfunction "B_1") (pintype "passive"))
    )
    (net (code "297") (name "Net-(T3-C)") (class "Default")
      (node (ref "J33") (pin "3") (pinfunction "3_3") (pintype "passive"))
      (node (ref "T3") (pin "3") (pinfunction "C_3") (pintype "passive"))
    )
    (net (code "298") (name "Net-(T3-E)") (class "Default")
      (node (ref "J33") (pin "1") (pinfunction "1_1") (pintype "passive"))
      (node (ref "T3") (pin "2") (pinfunction "E_2") (pintype "passive"))
    )
    (net (code "299") (name "Net-(T4-B)") (class "Default")
      (node (ref "J34") (pin "2") (pinfunction "2_2") (pintype "passive"))
      (node (ref "T4") (pin "1") (pinfunction "B_1") (pintype "passive"))
    )
    (net (code "300") (name "Net-(T4-C)") (class "Default")
      (node (ref "J34") (pin "1") (pinfunction "1_1") (pintype "passive"))
      (node (ref "T4") (pin "3") (pinfunction "C_3") (pintype "passive"))
    )
    (net (code "301") (name "Net-(T4-E)") (class "Default")
      (node (ref "J34") (pin "3") (pinfunction "3_3") (pintype "passive"))
      (node (ref "T4") (pin "2") (pinfunction "E_2") (pintype "passive"))
    )
    (net (code "302") (name "Net-(T5-B)") (class "Default")
      (node (ref "J35") (pin "2") (pinfunction "2_2") (pintype "passive"))
      (node (ref "T5") (pin "1") (pinfunction "B_1") (pintype "passive"))
    )
    (net (code "303") (name "Net-(T5-C)") (class "Default")
      (node (ref "J35") (pin "1") (pinfunction "1_1") (pintype "passive"))
      (node (ref "T5") (pin "3") (pinfunction "C_3") (pintype "passive"))
    )
    (net (code "304") (name "Net-(T5-E)") (class "Default")
      (node (ref "J35") (pin "3") (pinfunction "3_3") (pintype "passive"))
      (node (ref "T5") (pin "2") (pinfunction "E_2") (pintype "passive"))
    )
    (net (code "305") (name "Net-(U$1-A)") (class "Default")
      (node (ref "R41") (pin "2") (pinfunction "2_2") (pintype "passive"))
      (node (ref "U$1") (pin "7") (pinfunction "A_7") (pintype "bidirectional"))
    )
    (net (code "306") (name "Net-(U$1-B)") (class "Default")
      (node (ref "R42") (pin "2") (pinfunction "2_2") (pintype "passive"))
      (node (ref "U$1") (pin "6") (pinfunction "B_6") (pintype "bidirectional"))
    )
    (net (code "307") (name "Net-(U$1-C)") (class "Default")
      (node (ref "R43") (pin "2") (pinfunction "2_2") (pintype "passive"))
      (node (ref "U$1") (pin "4") (pinfunction "C_4") (pintype "bidirectional"))
    )
    (net (code "308") (name "Net-(U$1-D)") (class "Default")
      (node (ref "R44") (pin "2") (pinfunction "2_2") (pintype "passive"))
      (node (ref "U$1") (pin "2") (pinfunction "D_2") (pintype "bidirectional"))
    )
    (net (code "309") (name "Net-(U$1-E)") (class "Default")
      (node (ref "R45") (pin "2") (pinfunction "2_2") (pintype "passive"))
      (node (ref "U$1") (pin "1") (pinfunction "E_1") (pintype "bidirectional"))
    )
    (net (code "310") (name "Net-(U$1-F)") (class "Default")
      (node (ref "R46") (pin "2") (pinfunction "2_2") (pintype "passive"))
      (node (ref "U$1") (pin "9") (pinfunction "F_9") (pintype "bidirectional"))
    )
    (net (code "311") (name "Net-(U$1-G)") (class "Default")
      (node (ref "R47") (pin "2") (pinfunction "2_2") (pintype "passive"))
      (node (ref "U$1") (pin "10") (pinfunction "G_10") (pintype "bidirectional"))
    )
    (net (code "312") (name "Net-(U1-XOUT)") (class "Default")
      (node (ref "C29") (pin "1") (pinfunction "1_1") (pintype "passive"))
      (node (ref "J25") (pin "1") (pinfunction "1_1") (pintype "passive"))
      (node (ref "U1") (pin "12") (pinfunction "XOUT_12") (pintype "bidirectional"))
    )
    (net (code "313") (name "Net-(U1-YOUT)") (class "Default")
      (node (ref "C30") (pin "1") (pinfunction "1_1") (pintype "passive"))
      (node (ref "J25") (pin "2") (pinfunction "2_2") (pintype "passive"))
      (node (ref "U1") (pin "10") (pinfunction "YOUT_10") (pintype "bidirectional"))
    )
    (net (code "314") (name "Net-(U1-ZOUT)") (class "Default")
      (node (ref "C31") (pin "1") (pinfunction "1_1") (pintype "passive"))
      (node (ref "J25") (pin "3") (pinfunction "3_3") (pintype "passive"))
      (node (ref "U1") (pin "8") (pinfunction "ZOUT_8") (pintype "bidirectional"))
    )
    (net (code "315") (name "Net-(U3-OUT)") (class "Default")
      (node (ref "C39") (pin "1") (pinfunction "1_1") (pintype "passive"))
      (node (ref "F1") (pin "2") (pinfunction "2_2") (pintype "passive"))
      (node (ref "U3") (pin "2") (pinfunction "OUT_2") (pintype "output"))
    )
    (net (code "316") (name "O1A") (class "Default")
      (node (ref "ARR3") (pin "1") (pinfunction "1_1") (pintype "passive"))
      (node (ref "IC15") (pin "1") (pinfunction "1A_1") (pintype "input"))
      (node (ref "U$3") (pin "1") (pinfunction "1_1") (pintype "passive"))
    )
    (net (code "317") (name "O1B") (class "Default")
      (node (ref "ARR3") (pin "2") (pinfunction "1_2") (pintype "passive"))
      (node (ref "IC15") (pin "2") (pinfunction "1B_2") (pintype "input"))
      (node (ref "U$3") (pin "2") (pinfunction "2_2") (pintype "passive"))
    )
    (net (code "318") (name "O1Y") (class "Default")
      (node (ref "IC15") (pin "3") (pinfunction "1Y_3") (pintype "output"))
      (node (ref "J43") (pin "1") (pinfunction "1_1") (pintype "passive"))
    )
    (net (code "319") (name "O2A") (class "Default")
      (node (ref "ARR3") (pin "3") (pinfunction "1_3") (pintype "passive"))
      (node (ref "IC15") (pin "4") (pinfunction "2A_4") (pintype "input"))
      (node (ref "U$3") (pin "3") (pinfunction "3_3") (pintype "passive"))
    )
    (net (code "320") (name "O2B") (class "Default")
      (node (ref "ARR3") (pin "4") (pinfunction "1_4") (pintype "passive"))
      (node (ref "IC15") (pin "5") (pinfunction "2B_5") (pintype "input"))
      (node (ref "U$3") (pin "4") (pinfunction "4_4") (pintype "passive"))
    )
    (net (code "321") (name "O2Y") (class "Default")
      (node (ref "IC15") (pin "6") (pinfunction "2Y_6") (pintype "output"))
      (node (ref "J43") (pin "2") (pinfunction "2_2") (pintype "passive"))
    )
    (net (code "322") (name "O3A") (class "Default")
      (node (ref "ARR4") (pin "1") (pinfunction "1_1") (pintype "passive"))
      (node (ref "IC15") (pin "9") (pinfunction "3A_9") (pintype "input"))
      (node (ref "U$3") (pin "5") (pinfunction "5_5") (pintype "passive"))
    )
    (net (code "323") (name "O3B") (class "Default")
      (node (ref "ARR4") (pin "2") (pinfunction "1_2") (pintype "passive"))
      (node (ref "IC15") (pin "10") (pinfunction "3B_10") (pintype "input"))
      (node (ref "U$3") (pin "6") (pinfunction "6_6") (pintype "passive"))
    )
    (net (code "324") (name "O3Y") (class "Default")
      (node (ref "IC15") (pin "8") (pinfunction "3Y_8") (pintype "output"))
      (node (ref "J43") (pin "3") (pinfunction "3_3") (pintype "passive"))
    )
    (net (code "325") (name "O4A") (class "Default")
      (node (ref "ARR4") (pin "3") (pinfunction "1_3") (pintype "passive"))
      (node (ref "IC15") (pin "12") (pinfunction "4A_12") (pintype "input"))
      (node (ref "U$3") (pin "7") (pinfunction "7_7") (pintype "passive"))
    )
    (net (code "326") (name "O4B") (class "Default")
      (node (ref "ARR4") (pin "4") (pinfunction "1_4") (pintype "passive"))
      (node (ref "IC15") (pin "13") (pinfunction "4B_13") (pintype "input"))
      (node (ref "U$3") (pin "8") (pinfunction "8_8") (pintype "passive"))
    )
    (net (code "327") (name "O4Y") (class "Default")
      (node (ref "IC15") (pin "11") (pinfunction "4Y_11") (pintype "output"))
      (node (ref "J43") (pin "4") (pinfunction "4_4") (pintype "passive"))
    )
    (net (code "328") (name "OUT_L+") (class "Default")
      (node (ref "IC11") (pin "1") (pinfunction "+OUT_L_1") (pintype "input"))
      (node (ref "J3") (pin "1") (pinfunction "1_1") (pintype "passive"))
    )
    (net (code "329") (name "OUT_L-") (class "Default")
      (node (ref "IC11") (pin "3") (pinfunction "-OUT_L_3") (pintype "input"))
      (node (ref "J3") (pin "2") (pinfunction "2_2") (pintype "passive"))
    )
    (net (code "330") (name "OUT_R+") (class "Default")
      (node (ref "IC11") (pin "16") (pinfunction "+OUT_R_16") (pintype "output"))
      (node (ref "J3") (pin "3") (pinfunction "3_3") (pintype "passive"))
    )
    (net (code "331") (name "OUT_R-") (class "Default")
      (node (ref "IC11") (pin "14") (pinfunction "-OUT_R_14") (pintype "output"))
      (node (ref "J3") (pin "4") (pinfunction "4_4") (pintype "passive"))
    )
    (net (code "332") (name "SA'") (class "Default")
      (node (ref "R41") (pin "1") (pinfunction "1_1") (pintype "passive"))
      (node (ref "U$7") (pin "13") (pinfunction "A_13") (pintype "output"))
    )
    (net (code "333") (name "SB'") (class "Default")
      (node (ref "R42") (pin "1") (pinfunction "1_1") (pintype "passive"))
      (node (ref "U$7") (pin "12") (pinfunction "B_12") (pintype "output"))
    )
    (net (code "334") (name "SC'") (class "Default")
      (node (ref "R43") (pin "1") (pinfunction "1_1") (pintype "passive"))
      (node (ref "U$7") (pin "11") (pinfunction "C_11") (pintype "output"))
    )
    (net (code "335") (name "SD'") (class "Default")
      (node (ref "R44") (pin "1") (pinfunction "1_1") (pintype "passive"))
      (node (ref "U$7") (pin "10") (pinfunction "D_10") (pintype "output"))
    )
    (net (code "336") (name "SE'") (class "Default")
      (node (ref "R45") (pin "1") (pinfunction "1_1") (pintype "passive"))
      (node (ref "U$7") (pin "9") (pinfunction "E_9") (pintype "input"))
    )
    (net (code "337") (name "SF'") (class "Default")
      (node (ref "R46") (pin "1") (pinfunction "1_1") (pintype "passive"))
      (node (ref "U$7") (pin "15") (pinfunction "F_15") (pintype "input"))
    )
    (net (code "338") (name "SG'") (class "Default")
      (node (ref "R47") (pin "1") (pinfunction "1_1") (pintype "passive"))
      (node (ref "U$7") (pin "14") (pinfunction "G_14") (pintype "input"))
    )
    (net (code "339") (name "SHDN") (class "Default")
      (node (ref "IC11") (pin "12") (pinfunction "SHND_12") (pintype "output"))
    )
    (net (code "340") (name "VBAT") (class "Default")
      (node (ref "C28") (pin "1") (pinfunction "1_1") (pintype "passive"))
      (node (ref "IC9") (pin "5") (pinfunction "BAT_5") (pintype "bidirectional"))
      (node (ref "J1") (pin "1") (pinfunction "+_1") (pintype "passive"))
      (node (ref "S1") (pin "6") (pinfunction "R2_6") (pintype "passive"))
    )
    (net (code "341") (name "VCC") (class "Default")
      (node (ref "C23") (pin "1") (pinfunction "1_1") (pintype "passive"))
      (node (ref "C24") (pin "1") (pinfunction "1_1") (pintype "passive"))
      (node (ref "C27") (pin "+") (pinfunction "+_+") (pintype "passive"))
      (node (ref "C32") (pin "1") (pinfunction "1_1") (pintype "passive"))
      (node (ref "F1") (pin "1") (pinfunction "1_1") (pintype "passive"))
      (node (ref "IC11") (pin "13") (pinfunction "PVDD1_13") (pintype "output"))
      (node (ref "IC11") (pin "4") (pinfunction "PVDD_4") (pintype "input"))
      (node (ref "IC11") (pin "6") (pinfunction "VDD_6") (pintype "input"))
      (node (ref "IC13") (pin "14") (pinfunction "VCC_14") (pintype "input"))
      (node (ref "IC14") (pin "14") (pinfunction "VCC_14") (pintype "input"))
      (node (ref "IC15") (pin "14") (pinfunction "VCC_14") (pintype "input"))
      (node (ref "IC3") (pin "4") (pinfunction "VCC_4") (pintype "input"))
      (node (ref "IC4") (pin "4") (pinfunction "VCC_4") (pintype "input"))
      (node (ref "IC6") (pin "10") (pinfunction "S_10") (pintype "input"))
      (node (ref "IC6") (pin "14") (pinfunction "R_14") (pintype "input"))
      (node (ref "IC6") (pin "15") (pinfunction "R_15") (pintype "input"))
      (node (ref "IC6") (pin "16") (pinfunction "VDD_16") (pintype "power_in"))
      (node (ref "IC6") (pin "4") (pinfunction "S_4") (pintype "input"))
      (node (ref "IC7") (pin "10") (pinfunction "S_10") (pintype "input"))
      (node (ref "IC7") (pin "14") (pinfunction "R_14") (pintype "input"))
      (node (ref "IC7") (pin "15") (pinfunction "R_15") (pintype "input"))
      (node (ref "IC7") (pin "16") (pinfunction "VDD_16") (pintype "power_in"))
      (node (ref "IC7") (pin "4") (pinfunction "S_4") (pintype "input"))
      (node (ref "IC8") (pin "4") (pinfunction "R_4") (pintype "input"))
      (node (ref "IC8") (pin "8") (pinfunction "V+_8") (pintype "power_in"))
      (node (ref "J19") (pin "1") (pinfunction "1_1") (pintype "passive"))
      (node (ref "J19") (pin "10") (pinfunction "10_10") (pintype "passive"))
      (node (ref "J19") (pin "11") (pinfunction "11_11") (pintype "passive"))
      (node (ref "J19") (pin "12") (pinfunction "12_12") (pintype "passive"))
      (node (ref "J19") (pin "13") (pinfunction "13_13") (pintype "passive"))
      (node (ref "J19") (pin "14") (pinfunction "14_14") (pintype "passive"))
      (node (ref "J19") (pin "15") (pinfunction "15_15") (pintype "passive"))
      (node (ref "J19") (pin "16") (pinfunction "16_16") (pintype "passive"))
      (node (ref "J19") (pin "17") (pinfunction "17_17") (pintype "passive"))
      (node (ref "J19") (pin "18") (pinfunction "18_18") (pintype "passive"))
      (node (ref "J19") (pin "19") (pinfunction "19_19") (pintype "passive"))
      (node (ref "J19") (pin "2") (pinfunction "2_2") (pintype "passive"))
      (node (ref "J19") (pin "20") (pinfunction "20_20") (pintype "passive"))
      (node (ref "J19") (pin "21") (pinfunction "21_21") (pintype "passive"))
      (node (ref "J19") (pin "22") (pinfunction "22_22") (pintype "passive"))
      (node (ref "J19") (pin "23") (pinfunction "23_23") (pintype "passive"))
      (node (ref "J19") (pin "24") (pinfunction "24_24") (pintype "passive"))
      (node (ref "J19") (pin "25") (pinfunction "25_25") (pintype "passive"))
      (node (ref "J19") (pin "26") (pinfunction "26_26") (pintype "passive"))
      (node (ref "J19") (pin "27") (pinfunction "27_27") (pintype "passive"))
      (node (ref "J19") (pin "28") (pinfunction "28_28") (pintype "passive"))
      (node (ref "J19") (pin "29") (pinfunction "29_29") (pintype "passive"))
      (node (ref "J19") (pin "3") (pinfunction "3_3") (pintype "passive"))
      (node (ref "J19") (pin "30") (pinfunction "30_30") (pintype "passive"))
      (node (ref "J19") (pin "4") (pinfunction "4_4") (pintype "passive"))
      (node (ref "J19") (pin "5") (pinfunction "5_5") (pintype "passive"))
      (node (ref "J19") (pin "6") (pinfunction "6_6") (pintype "passive"))
      (node (ref "J19") (pin "7") (pinfunction "7_7") (pintype "passive"))
      (node (ref "J19") (pin "8") (pinfunction "8_8") (pintype "passive"))
      (node (ref "J19") (pin "9") (pinfunction "9_9") (pintype "passive"))
      (node (ref "R31") (pin "1") (pinfunction "1_1") (pintype "passive"))
      (node (ref "U$7") (pin "16") (pinfunction "VCC_16") (pintype "input"))
      (node (ref "U$7") (pin "3") (pinfunction "~{LT}_3") (pintype "input"))
      (node (ref "U$7") (pin "4") (pinfunction "~{BL}_4") (pintype "input"))
      (node (ref "U1") (pin "14") (pinfunction "VS_14") (pintype "bidirectional"))
      (node (ref "U1") (pin "15") (pinfunction "VS_15") (pintype "bidirectional"))
    )
    (net (code "342") (name "VREF") (class "Default")
      (node (ref "C25") (pin "1") (pinfunction "1_1") (pintype "passive"))
      (node (ref "IC11") (pin "8") (pinfunction "VREF_8") (pintype "input"))
    )
    (net (code "343") (name "V_USB") (class "Default")
      (node (ref "C37") (pin "1") (pinfunction "1_1") (pintype "passive"))
      (node (ref "IC9") (pin "4") (pinfunction "VCC_4") (pintype "bidirectional"))
      (node (ref "IC9") (pin "8") (pinfunction "CE_8") (pintype "bidirectional"))
      (node (ref "LED1") (pin "2") (pinfunction "A_2") (pintype "passive"))
      (node (ref "LED1") (pin "3") (pinfunction "A_3") (pintype "passive"))
      (node (ref "S1") (pin "3") (pinfunction "L2_3") (pintype "passive"))
      (node (ref "X8") (pin "VBUS") (pinfunction "VBUS_VBUS") (pintype "power_in"))
    )
    (net (code "344") (name "unconnected-(S1-L1-Pad1)") (class "Default")
      (node (ref "S1") (pin "1") (pinfunction "L1_1") (pintype "passive"))
    )
    (net (code "345") (name "unconnected-(S1-R1-Pad4)") (class "Default")
      (node (ref "S1") (pin "4") (pinfunction "R1_4") (pintype "passive"))
    )
    (net (code "346") (name "unconnected-(U$1-DP-Pad5)") (class "Default")
      (node (ref "U$1") (pin "5") (pinfunction "DP_5") (pintype "bidirectional"))
    )
    (net (code "347") (name "unconnected-(U1-ST-Pad2)") (class "Default")
      (node (ref "U1") (pin "2") (pinfunction "ST_2") (pintype "bidirectional"))
    )
  )
)
